# SA.net
KiCad netlist of a schematic drawn in EAGLE
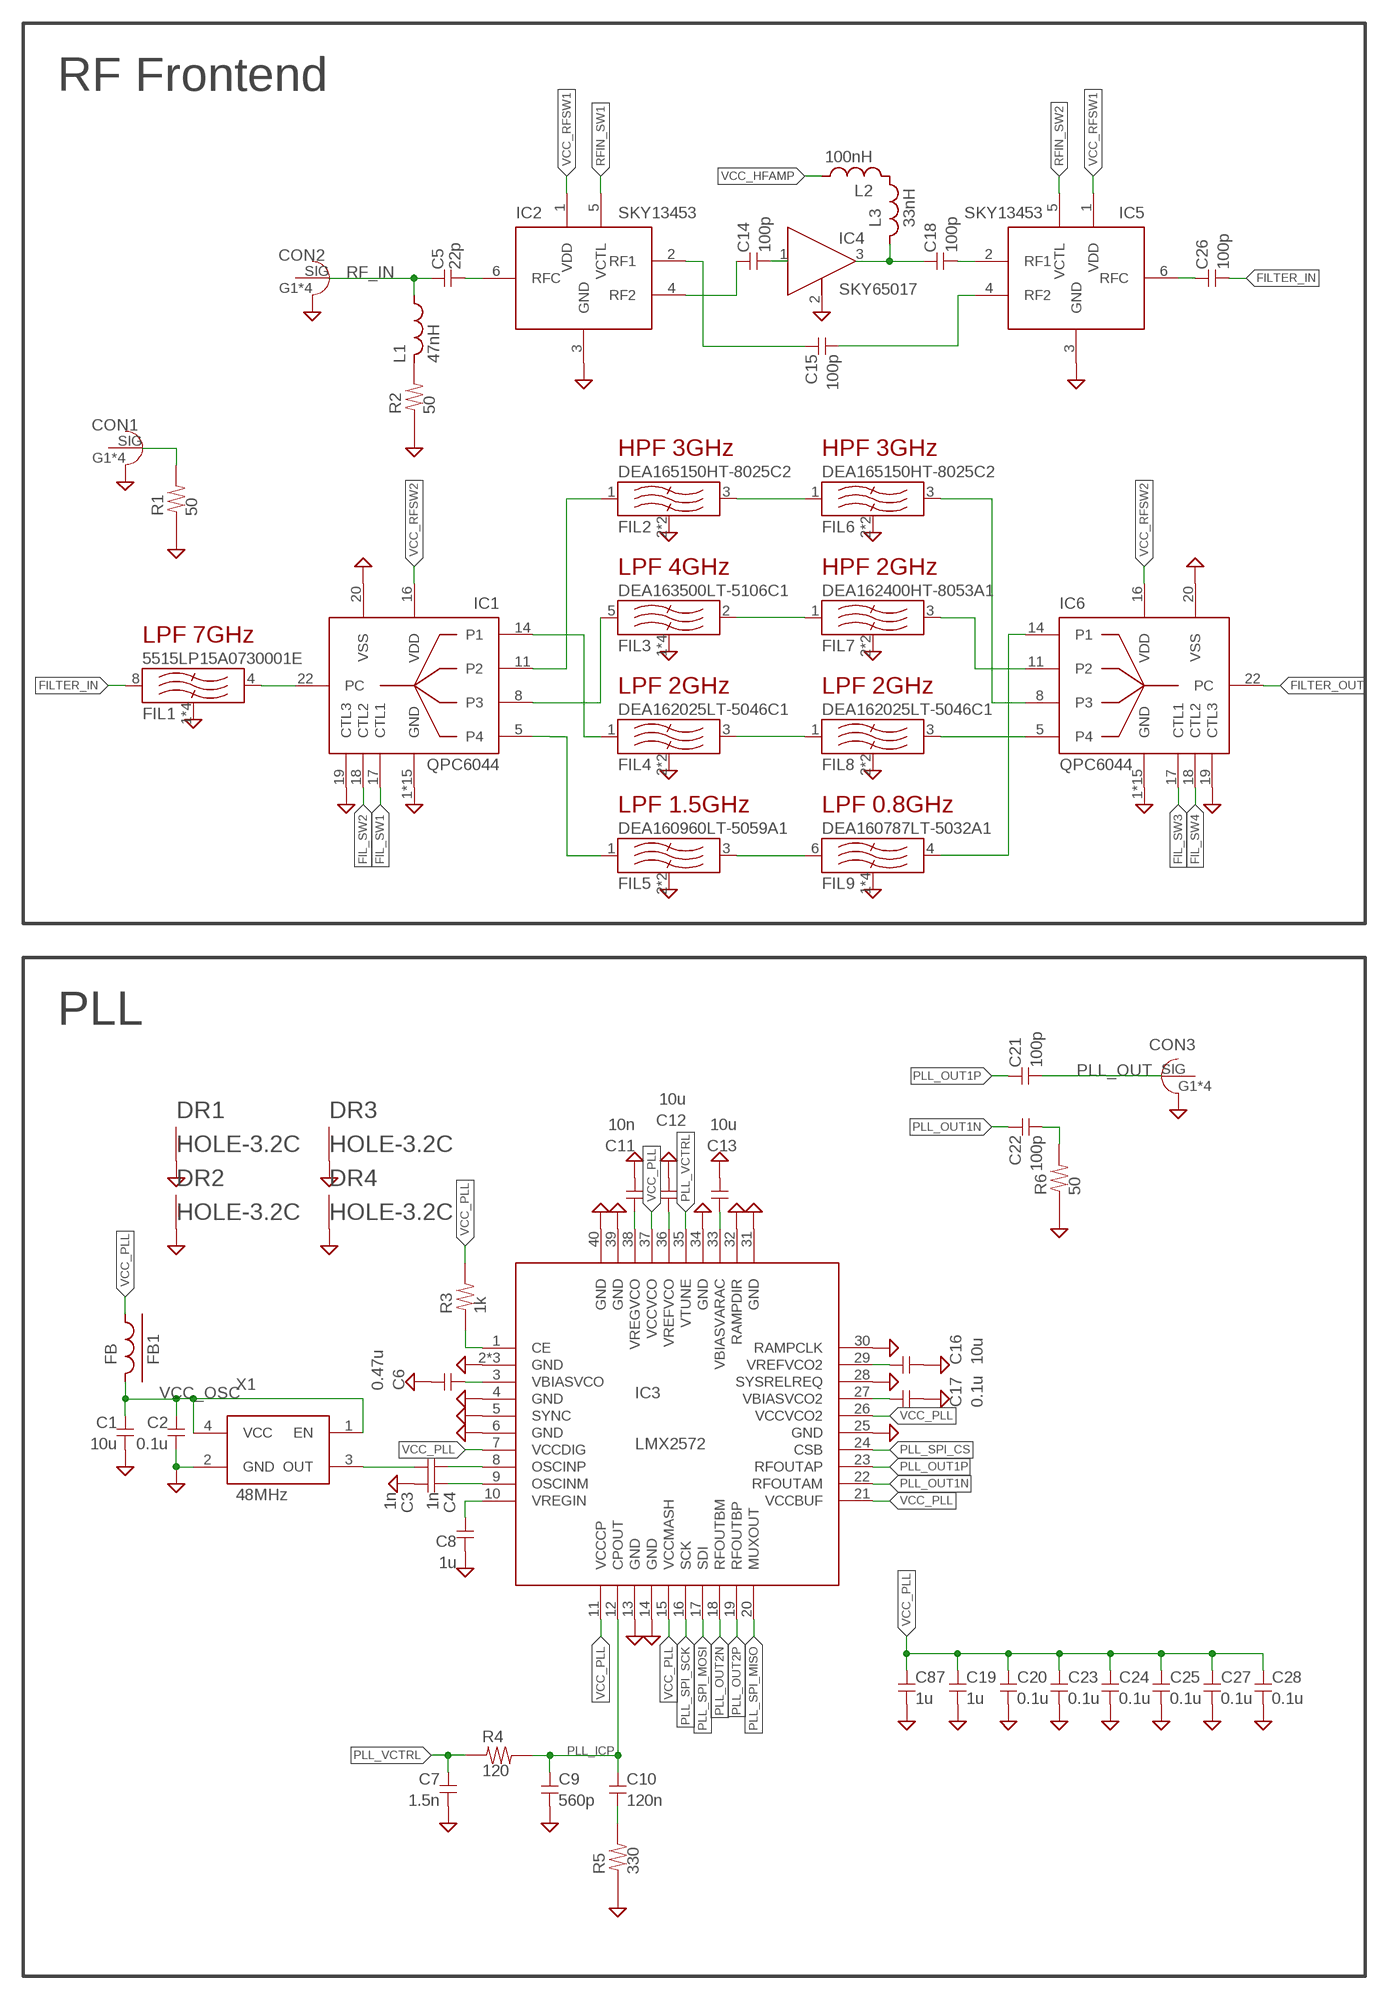
[diagram p0: schematic, sheet 1, part 1 of 2]
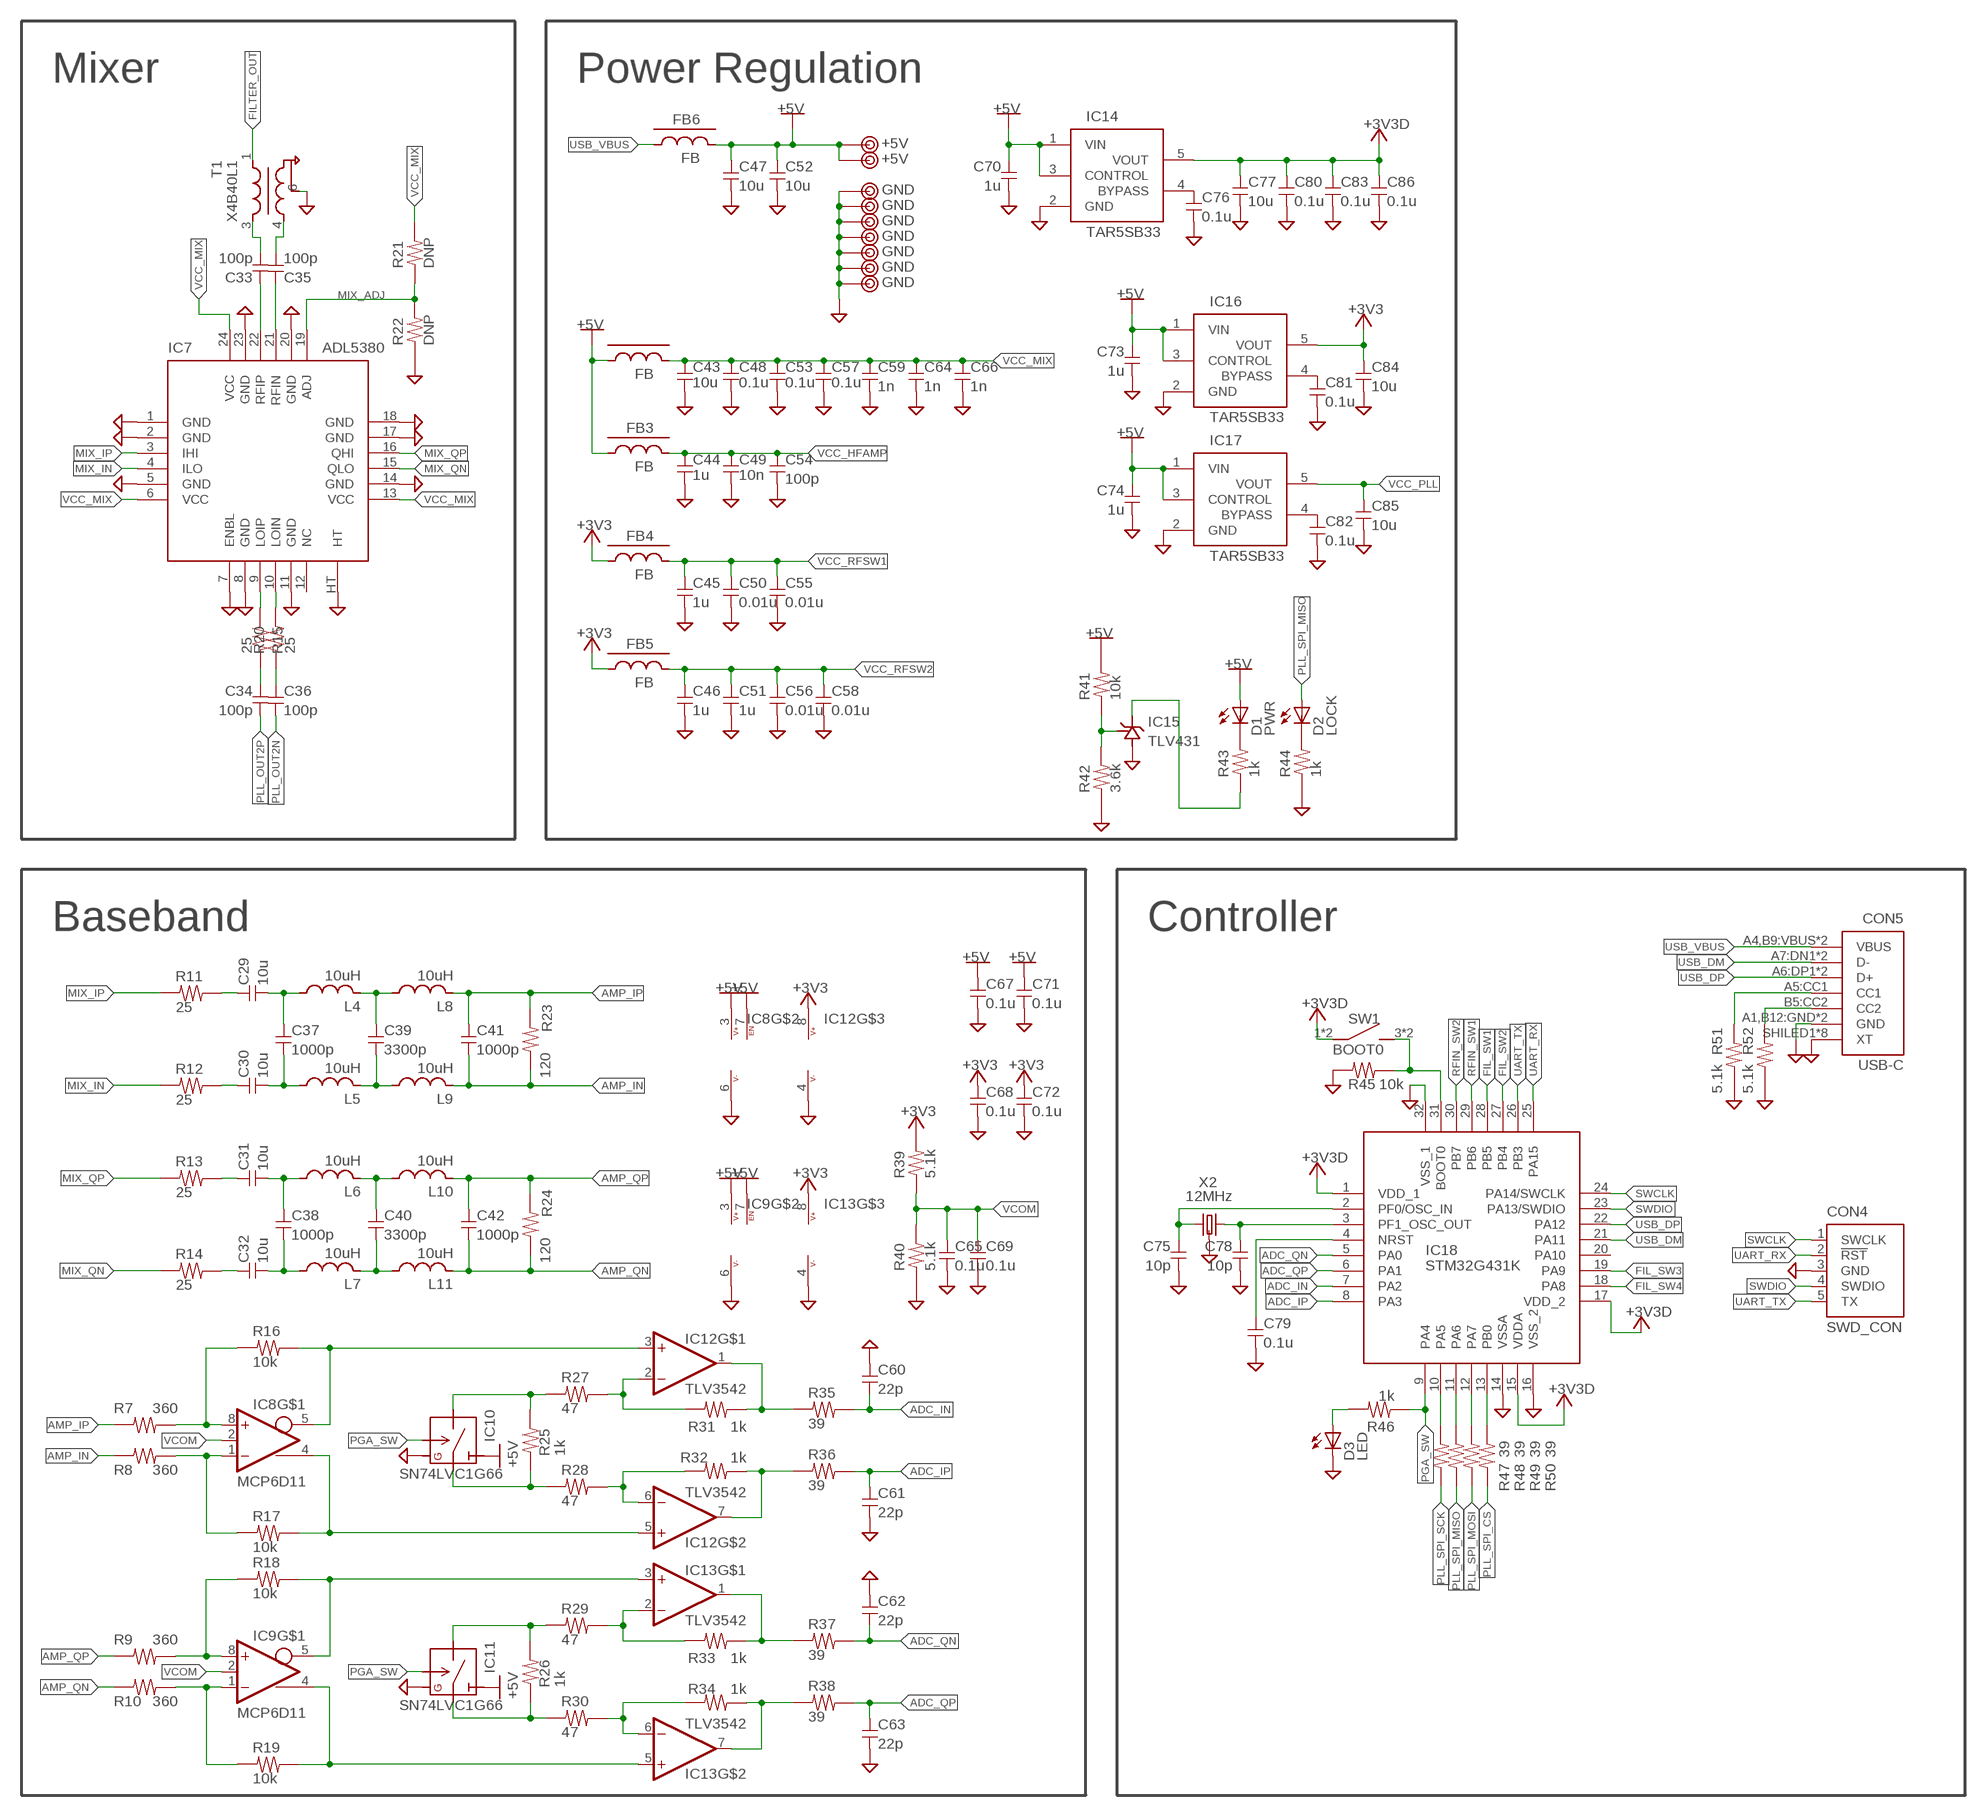
[diagram p1: schematic, sheet 1, part 2 of 2]

(export (version "E")
  (design (tool "Eeschema 10.0.6"))
  (components
    (comp (ref "C1")
      (value "10u")
      (footprint "eagle-import:2012")
      (libsource (lib "eagle-import") (part "C-2012"))
    )
    (comp (ref "C2")
      (value "0.1u")
      (footprint "eagle-import:1608C")
      (libsource (lib "eagle-import") (part "C-1608"))
    )
    (comp (ref "C3")
      (value "1n")
      (footprint "eagle-import:1005")
      (libsource (lib "eagle-import") (part "C-1005"))
    )
    (comp (ref "C4")
      (value "1n")
      (footprint "eagle-import:1005")
      (libsource (lib "eagle-import") (part "C-1005"))
    )
    (comp (ref "C5")
      (value "22p")
      (footprint "eagle-import:1005RF")
      (libsource (lib "eagle-import") (part "C-1005RF"))
    )
    (comp (ref "C6")
      (value "0.47u")
      (footprint "eagle-import:1608C")
      (libsource (lib "eagle-import") (part "C-1608"))
    )
    (comp (ref "C7")
      (value "1.5n")
      (footprint "eagle-import:1608C")
      (libsource (lib "eagle-import") (part "C-1608"))
    )
    (comp (ref "C8")
      (value "1u")
      (footprint "eagle-import:1608C")
      (libsource (lib "eagle-import") (part "C-1608"))
    )
    (comp (ref "C9")
      (value "560p")
      (footprint "eagle-import:1608C")
      (libsource (lib "eagle-import") (part "C-1608"))
    )
    (comp (ref "C10")
      (value "120n")
      (footprint "eagle-import:1608C")
      (libsource (lib "eagle-import") (part "C-1608"))
    )
    (comp (ref "C11")
      (value "10n")
      (footprint "eagle-import:1608C")
      (libsource (lib "eagle-import") (part "C-1608"))
    )
    (comp (ref "C12")
      (value "10u")
      (footprint "eagle-import:1608C")
      (libsource (lib "eagle-import") (part "C-1608"))
    )
    (comp (ref "C13")
      (value "10u")
      (footprint "eagle-import:1608C")
      (libsource (lib "eagle-import") (part "C-1608"))
    )
    (comp (ref "C14")
      (value "100p")
      (footprint "eagle-import:1005RF")
      (libsource (lib "eagle-import") (part "C-1005RF"))
    )
    (comp (ref "C15")
      (value "100p")
      (footprint "eagle-import:1005RF")
      (libsource (lib "eagle-import") (part "C-1005RF"))
    )
    (comp (ref "C16")
      (value "10u")
      (footprint "eagle-import:1608C")
      (libsource (lib "eagle-import") (part "C-1608"))
    )
    (comp (ref "C17")
      (value "0.1u")
      (footprint "eagle-import:1608C")
      (libsource (lib "eagle-import") (part "C-1608"))
    )
    (comp (ref "C18")
      (value "100p")
      (footprint "eagle-import:1005RF")
      (libsource (lib "eagle-import") (part "C-1005RF"))
    )
    (comp (ref "C19")
      (value "1u")
      (footprint "eagle-import:1608C")
      (libsource (lib "eagle-import") (part "C-1608"))
    )
    (comp (ref "C20")
      (value "0.1u")
      (footprint "eagle-import:1608C")
      (libsource (lib "eagle-import") (part "C-1608"))
    )
    (comp (ref "C21")
      (value "100p")
      (footprint "eagle-import:1005RF")
      (libsource (lib "eagle-import") (part "C-1005RF"))
    )
    (comp (ref "C22")
      (value "100p")
      (footprint "eagle-import:1005RF")
      (libsource (lib "eagle-import") (part "C-1005RF"))
    )
    (comp (ref "C23")
      (value "0.1u")
      (footprint "eagle-import:1608C")
      (libsource (lib "eagle-import") (part "C-1608"))
    )
    (comp (ref "C24")
      (value "0.1u")
      (footprint "eagle-import:1608C")
      (libsource (lib "eagle-import") (part "C-1608"))
    )
    (comp (ref "C25")
      (value "0.1u")
      (footprint "eagle-import:1608C")
      (libsource (lib "eagle-import") (part "C-1608"))
    )
    (comp (ref "C26")
      (value "100p")
      (footprint "eagle-import:1005RF")
      (libsource (lib "eagle-import") (part "C-1005RF"))
    )
    (comp (ref "C27")
      (value "0.1u")
      (footprint "eagle-import:1608C")
      (libsource (lib "eagle-import") (part "C-1608"))
    )
    (comp (ref "C28")
      (value "0.1u")
      (footprint "eagle-import:1608C")
      (libsource (lib "eagle-import") (part "C-1608"))
    )
    (comp (ref "C29")
      (value "10u")
      (footprint "eagle-import:1608C")
      (libsource (lib "eagle-import") (part "C-1608"))
    )
    (comp (ref "C30")
      (value "10u")
      (footprint "eagle-import:1608C")
      (libsource (lib "eagle-import") (part "C-1608"))
    )
    (comp (ref "C31")
      (value "10u")
      (footprint "eagle-import:1608C")
      (libsource (lib "eagle-import") (part "C-1608"))
    )
    (comp (ref "C32")
      (value "10u")
      (footprint "eagle-import:1608C")
      (libsource (lib "eagle-import") (part "C-1608"))
    )
    (comp (ref "C33")
      (value "100p")
      (footprint "eagle-import:1005RF")
      (libsource (lib "eagle-import") (part "C-1005RF"))
    )
    (comp (ref "C34")
      (value "100p")
      (footprint "eagle-import:1005RF")
      (libsource (lib "eagle-import") (part "C-1005RF"))
    )
    (comp (ref "C35")
      (value "100p")
      (footprint "eagle-import:1005RF")
      (libsource (lib "eagle-import") (part "C-1005RF"))
    )
    (comp (ref "C36")
      (value "100p")
      (footprint "eagle-import:1005RF")
      (libsource (lib "eagle-import") (part "C-1005RF"))
    )
    (comp (ref "C37")
      (value "1000p")
      (footprint "eagle-import:1608C")
      (libsource (lib "eagle-import") (part "C-1608"))
    )
    (comp (ref "C38")
      (value "1000p")
      (footprint "eagle-import:1608C")
      (libsource (lib "eagle-import") (part "C-1608"))
    )
    (comp (ref "C39")
      (value "3300p")
      (footprint "eagle-import:1608C")
      (libsource (lib "eagle-import") (part "C-1608"))
    )
    (comp (ref "C40")
      (value "3300p")
      (footprint "eagle-import:1608C")
      (libsource (lib "eagle-import") (part "C-1608"))
    )
    (comp (ref "C41")
      (value "1000p")
      (footprint "eagle-import:1608C")
      (libsource (lib "eagle-import") (part "C-1608"))
    )
    (comp (ref "C42")
      (value "1000p")
      (footprint "eagle-import:1608C")
      (libsource (lib "eagle-import") (part "C-1608"))
    )
    (comp (ref "C43")
      (value "10u")
      (footprint "eagle-import:2012")
      (libsource (lib "eagle-import") (part "C-2012"))
    )
    (comp (ref "C44")
      (value "1u")
      (footprint "eagle-import:1608C")
      (libsource (lib "eagle-import") (part "C-1608"))
    )
    (comp (ref "C45")
      (value "1u")
      (footprint "eagle-import:1608C")
      (libsource (lib "eagle-import") (part "C-1608"))
    )
    (comp (ref "C46")
      (value "1u")
      (footprint "eagle-import:1608C")
      (libsource (lib "eagle-import") (part "C-1608"))
    )
    (comp (ref "C47")
      (value "10u")
      (footprint "eagle-import:3216")
      (libsource (lib "eagle-import") (part "C-3216"))
    )
    (comp (ref "C48")
      (value "0.1u")
      (footprint "eagle-import:1608C")
      (libsource (lib "eagle-import") (part "C-1608"))
    )
    (comp (ref "C49")
      (value "10n")
      (footprint "eagle-import:1608C")
      (libsource (lib "eagle-import") (part "C-1608"))
    )
    (comp (ref "C50")
      (value "0.01u")
      (footprint "eagle-import:1608C")
      (libsource (lib "eagle-import") (part "C-1608"))
    )
    (comp (ref "C51")
      (value "1u")
      (footprint "eagle-import:1608C")
      (libsource (lib "eagle-import") (part "C-1608"))
    )
    (comp (ref "C52")
      (value "10u")
      (footprint "eagle-import:2012")
      (libsource (lib "eagle-import") (part "C-2012"))
    )
    (comp (ref "C53")
      (value "0.1u")
      (footprint "eagle-import:1608C")
      (libsource (lib "eagle-import") (part "C-1608"))
    )
    (comp (ref "C54")
      (value "100p")
      (footprint "eagle-import:1005")
      (libsource (lib "eagle-import") (part "C-1005"))
    )
    (comp (ref "C55")
      (value "0.01u")
      (footprint "eagle-import:1608C")
      (libsource (lib "eagle-import") (part "C-1608"))
    )
    (comp (ref "C56")
      (value "0.01u")
      (footprint "eagle-import:1608C")
      (libsource (lib "eagle-import") (part "C-1608"))
    )
    (comp (ref "C57")
      (value "0.1u")
      (footprint "eagle-import:1608C")
      (libsource (lib "eagle-import") (part "C-1608"))
    )
    (comp (ref "C58")
      (value "0.01u")
      (footprint "eagle-import:1608C")
      (libsource (lib "eagle-import") (part "C-1608"))
    )
    (comp (ref "C59")
      (value "1n")
      (footprint "eagle-import:1005")
      (libsource (lib "eagle-import") (part "C-1005"))
    )
    (comp (ref "C60")
      (value "22p")
      (footprint "eagle-import:1608C")
      (libsource (lib "eagle-import") (part "C-1608"))
    )
    (comp (ref "C61")
      (value "22p")
      (footprint "eagle-import:1608C")
      (libsource (lib "eagle-import") (part "C-1608"))
    )
    (comp (ref "C62")
      (value "22p")
      (footprint "eagle-import:1608C")
      (libsource (lib "eagle-import") (part "C-1608"))
    )
    (comp (ref "C63")
      (value "22p")
      (footprint "eagle-import:1608C")
      (libsource (lib "eagle-import") (part "C-1608"))
    )
    (comp (ref "C64")
      (value "1n")
      (footprint "eagle-import:1005")
      (libsource (lib "eagle-import") (part "C-1005"))
    )
    (comp (ref "C65")
      (value "0.1u")
      (footprint "eagle-import:1608C")
      (libsource (lib "eagle-import") (part "C-1608"))
    )
    (comp (ref "C66")
      (value "1n")
      (footprint "eagle-import:1005")
      (libsource (lib "eagle-import") (part "C-1005"))
    )
    (comp (ref "C67")
      (value "0.1u")
      (footprint "eagle-import:1608C")
      (libsource (lib "eagle-import") (part "C-1608"))
    )
    (comp (ref "C68")
      (value "0.1u")
      (footprint "eagle-import:1608C")
      (libsource (lib "eagle-import") (part "C-1608"))
    )
    (comp (ref "C69")
      (value "0.1u")
      (footprint "eagle-import:1608C")
      (libsource (lib "eagle-import") (part "C-1608"))
    )
    (comp (ref "C70")
      (value "1u")
      (footprint "eagle-import:1608C")
      (libsource (lib "eagle-import") (part "C-1608"))
    )
    (comp (ref "C71")
      (value "0.1u")
      (footprint "eagle-import:1608C")
      (libsource (lib "eagle-import") (part "C-1608"))
    )
    (comp (ref "C72")
      (value "0.1u")
      (footprint "eagle-import:1608C")
      (libsource (lib "eagle-import") (part "C-1608"))
    )
    (comp (ref "C73")
      (value "1u")
      (footprint "eagle-import:1608C")
      (libsource (lib "eagle-import") (part "C-1608"))
    )
    (comp (ref "C74")
      (value "1u")
      (footprint "eagle-import:1608C")
      (libsource (lib "eagle-import") (part "C-1608"))
    )
    (comp (ref "C75")
      (value "10p")
      (footprint "eagle-import:1608C")
      (libsource (lib "eagle-import") (part "C-1608"))
    )
    (comp (ref "C76")
      (value "0.1u")
      (footprint "eagle-import:1608C")
      (libsource (lib "eagle-import") (part "C-1608"))
    )
    (comp (ref "C77")
      (value "10u")
      (footprint "eagle-import:2012")
      (libsource (lib "eagle-import") (part "C-2012"))
    )
    (comp (ref "C78")
      (value "10p")
      (footprint "eagle-import:1608C")
      (libsource (lib "eagle-import") (part "C-1608"))
    )
    (comp (ref "C79")
      (value "0.1u")
      (footprint "eagle-import:1608C")
      (libsource (lib "eagle-import") (part "C-1608"))
    )
    (comp (ref "C80")
      (value "0.1u")
      (footprint "eagle-import:1608C")
      (libsource (lib "eagle-import") (part "C-1608"))
    )
    (comp (ref "C81")
      (value "0.1u")
      (footprint "eagle-import:1608C")
      (libsource (lib "eagle-import") (part "C-1608"))
    )
    (comp (ref "C82")
      (value "0.1u")
      (footprint "eagle-import:1608C")
      (libsource (lib "eagle-import") (part "C-1608"))
    )
    (comp (ref "C83")
      (value "0.1u")
      (footprint "eagle-import:1608C")
      (libsource (lib "eagle-import") (part "C-1608"))
    )
    (comp (ref "C84")
      (value "10u")
      (footprint "eagle-import:2012")
      (libsource (lib "eagle-import") (part "C-2012"))
    )
    (comp (ref "C85")
      (value "10u")
      (footprint "eagle-import:2012")
      (libsource (lib "eagle-import") (part "C-2012"))
    )
    (comp (ref "C86")
      (value "0.1u")
      (footprint "eagle-import:1608C")
      (libsource (lib "eagle-import") (part "C-1608"))
    )
    (comp (ref "C87")
      (value "1u")
      (footprint "eagle-import:1608C")
      (libsource (lib "eagle-import") (part "C-1608"))
    )
    (comp (ref "CON1")
      (value "DM_L")
      (footprint "eagle-import:SMA-EDGE")
      (libsource (lib "eagle-import") (part "SMA-142-0701-801"))
    )
    (comp (ref "CON2")
      (value "RF_IN")
      (footprint "eagle-import:SMA-EDGE")
      (libsource (lib "eagle-import") (part "SMA-142-0701-801"))
    )
    (comp (ref "CON3")
      (value "PLL_OUT")
      (footprint "eagle-import:SMA-EDGE")
      (libsource (lib "eagle-import") (part "SMA-142-0701-801"))
    )
    (comp (ref "CON4")
      (value "SWD_CON")
      (footprint "eagle-import:SWD_CON")
      (libsource (lib "eagle-import") (part "SWD_CON"))
    )
    (comp (ref "CON5")
      (value "USB-C")
      (footprint "eagle-import:5077CR-16-SMC2-BK-TR")
      (libsource (lib "eagle-import") (part "USB-C"))
    )
    (comp (ref "D1")
      (value "PWR")
      (footprint "eagle-import:D1608")
      (libsource (lib "eagle-import") (part "LED-SMD1608"))
    )
    (comp (ref "D2")
      (value "LOCK")
      (footprint "eagle-import:D1608")
      (libsource (lib "eagle-import") (part "LED-SMD1608"))
    )
    (comp (ref "D3")
      (value "LED")
      (footprint "eagle-import:D1608")
      (libsource (lib "eagle-import") (part "LED-SMD1608"))
    )
    (comp (ref "DR1")
      (value "HOLE-3.2C")
      (footprint "eagle-import:HOLE_3.2_CON2")
      (libsource (lib "eagle-import") (part "HOLE-3.2C"))
    )
    (comp (ref "DR2")
      (value "HOLE-3.2C")
      (footprint "eagle-import:HOLE_3.2_CON2")
      (libsource (lib "eagle-import") (part "HOLE-3.2C"))
    )
    (comp (ref "DR3")
      (value "HOLE-3.2C")
      (footprint "eagle-import:HOLE_3.2_CON2")
      (libsource (lib "eagle-import") (part "HOLE-3.2C"))
    )
    (comp (ref "DR4")
      (value "HOLE-3.2C")
      (footprint "eagle-import:HOLE_3.2_CON2")
      (libsource (lib "eagle-import") (part "HOLE-3.2C"))
    )
    (comp (ref "FB1")
      (value "FB")
      (footprint "eagle-import:1608-FB")
      (libsource (lib "eagle-import") (part "FB-1608FB"))
    )
    (comp (ref "FB2")
      (value "FB")
      (footprint "eagle-import:1608-FB")
      (libsource (lib "eagle-import") (part "FB-1608FB"))
    )
    (comp (ref "FB3")
      (value "FB")
      (footprint "eagle-import:1608-FB")
      (libsource (lib "eagle-import") (part "FB-1608FB"))
    )
    (comp (ref "FB4")
      (value "FB")
      (footprint "eagle-import:1608-FB")
      (libsource (lib "eagle-import") (part "FB-1608FB"))
    )
    (comp (ref "FB5")
      (value "FB")
      (footprint "eagle-import:1608-FB")
      (libsource (lib "eagle-import") (part "FB-1608FB"))
    )
    (comp (ref "FB6")
      (value "FB")
      (footprint "eagle-import:2012-R")
      (libsource (lib "eagle-import") (part "FB-2012-FB"))
    )
    (comp (ref "FIL1")
      (value "5515LP15A0730001E")
      (footprint "eagle-import:RF-FILTER-2012-JOHANSON")
      (libsource (lib "eagle-import") (part "RF-FILTER-2012-JOHANSON"))
    )
    (comp (ref "FIL2")
      (value "DEA165150HT-8025C2")
      (footprint "eagle-import:RF-FILTER-1608-TDK")
      (libsource (lib "eagle-import") (part "RF-FILTER-1608-TDK"))
    )
    (comp (ref "FIL3")
      (value "DEA163500LT-5106C1")
      (footprint "eagle-import:RF-FILTER-1608-TDK2")
      (libsource (lib "eagle-import") (part "RF-FILTER-1608-TDK3"))
    )
    (comp (ref "FIL4")
      (value "DEA162025LT-5046C1")
      (footprint "eagle-import:RF-FILTER-1608-TDK")
      (libsource (lib "eagle-import") (part "RF-FILTER-1608-TDK"))
    )
    (comp (ref "FIL5")
      (value "DEA160960LT-5059A1")
      (footprint "eagle-import:RF-FILTER-1608-TDK")
      (libsource (lib "eagle-import") (part "RF-FILTER-1608-TDK"))
    )
    (comp (ref "FIL6")
      (value "DEA165150HT-8025C2")
      (footprint "eagle-import:RF-FILTER-1608-TDK")
      (libsource (lib "eagle-import") (part "RF-FILTER-1608-TDK"))
    )
    (comp (ref "FIL7")
      (value "DEA162400HT-8053A1")
      (footprint "eagle-import:RF-FILTER-1608-TDK")
      (libsource (lib "eagle-import") (part "RF-FILTER-1608-TDK"))
    )
    (comp (ref "FIL8")
      (value "DEA162025LT-5046C1")
      (footprint "eagle-import:RF-FILTER-1608-TDK")
      (libsource (lib "eagle-import") (part "RF-FILTER-1608-TDK"))
    )
    (comp (ref "FIL9")
      (value "DEA160787LT-5032A1")
      (footprint "eagle-import:RF-FILTER-1608-TDK2")
      (libsource (lib "eagle-import") (part "RF-FILTER-1608-TDK2"))
    )
    (comp (ref "IC1")
      (value "QPC6044")
      (footprint "eagle-import:QFN24-QPC6044")
      (libsource (lib "eagle-import") (part "QPC6044"))
    )
    (comp (ref "IC2")
      (value "SKY13453")
      (footprint "eagle-import:SKY13453")
      (libsource (lib "eagle-import") (part "SKY13453"))
    )
    (comp (ref "IC3")
      (value "LMX2572")
      (footprint "eagle-import:QFN40-LMX")
      (libsource (lib "eagle-import") (part "LMX2572"))
    )
    (comp (ref "IC4")
      (value "SKY65017")
      (footprint "eagle-import:SOT89-RF")
      (libsource (lib "eagle-import") (part "RF_AMP"))
    )
    (comp (ref "IC5")
      (value "SKY13453")
      (footprint "eagle-import:SKY13453")
      (libsource (lib "eagle-import") (part "SKY13453"))
    )
    (comp (ref "IC6")
      (value "QPC6044")
      (footprint "eagle-import:QFN24-QPC6044")
      (libsource (lib "eagle-import") (part "QPC6044"))
    )
    (comp (ref "IC7")
      (value "ADL5380")
      (footprint "eagle-import:LFCSP24")
      (libsource (lib "eagle-import") (part "ADL5380"))
    )
    (comp (ref "IC8")
      (value "MCP6D11")
      (footprint "eagle-import:MSOP8")
      (libsource (lib "eagle-import") (part "OPA-DIFF-MSOP"))
    )
    (comp (ref "IC9")
      (value "MCP6D11")
      (footprint "eagle-import:MSOP8")
      (libsource (lib "eagle-import") (part "OPA-DIFF-MSOP"))
    )
    (comp (ref "IC10")
      (value "SN74LVC1G66")
      (footprint "eagle-import:SOT23-5-2")
      (libsource (lib "eagle-import") (part "SN74LVC1G66"))
    )
    (comp (ref "IC11")
      (value "SN74LVC1G66")
      (footprint "eagle-import:SOT23-5-2")
      (libsource (lib "eagle-import") (part "SN74LVC1G66"))
    )
    (comp (ref "IC12")
      (value "TLV3542")
      (footprint "eagle-import:SOP8-3")
      (libsource (lib "eagle-import") (part "OPA-2-SOP"))
    )
    (comp (ref "IC13")
      (value "TLV3542")
      (footprint "eagle-import:SOP8-3")
      (libsource (lib "eagle-import") (part "OPA-2-SOP"))
    )
    (comp (ref "IC14")
      (value "TAR5SB33")
      (footprint "eagle-import:SOT23-5")
      (libsource (lib "eagle-import") (part "TAR5SB33"))
    )
    (comp (ref "IC15")
      (value "TLV431")
      (footprint "eagle-import:SC59")
      (libsource (lib "eagle-import") (part "TL431-SC59"))
    )
    (comp (ref "IC16")
      (value "TAR5SB33")
      (footprint "eagle-import:SOT23-5")
      (libsource (lib "eagle-import") (part "TAR5SB33"))
    )
    (comp (ref "IC17")
      (value "TAR5SB33")
      (footprint "eagle-import:SOT23-5")
      (libsource (lib "eagle-import") (part "TAR5SB33"))
    )
    (comp (ref "IC18")
      (value "STM32G431K")
      (footprint "eagle-import:TQFP32-08")
      (libsource (lib "eagle-import") (part "STM32G431KB"))
    )
    (comp (ref "L1")
      (value "47nH")
      (footprint "eagle-import:1005RF")
      (libsource (lib "eagle-import") (part "L-1005RF"))
    )
    (comp (ref "L2")
      (value "100nH")
      (footprint "eagle-import:1608-L")
      (libsource (lib "eagle-import") (part "L-1608"))
    )
    (comp (ref "L3")
      (value "33nH")
      (footprint "eagle-import:1005RF")
      (libsource (lib "eagle-import") (part "L-1005RF"))
    )
    (comp (ref "L4")
      (value "10uH")
      (footprint "eagle-import:2012-R")
      (libsource (lib "eagle-import") (part "L-2012"))
    )
    (comp (ref "L5")
      (value "10uH")
      (footprint "eagle-import:2012-R")
      (libsource (lib "eagle-import") (part "L-2012"))
    )
    (comp (ref "L6")
      (value "10uH")
      (footprint "eagle-import:2012-R")
      (libsource (lib "eagle-import") (part "L-2012"))
    )
    (comp (ref "L7")
      (value "10uH")
      (footprint "eagle-import:2012-R")
      (libsource (lib "eagle-import") (part "L-2012"))
    )
    (comp (ref "L8")
      (value "10uH")
      (footprint "eagle-import:2012-R")
      (libsource (lib "eagle-import") (part "L-2012"))
    )
    (comp (ref "L9")
      (value "10uH")
      (footprint "eagle-import:2012-R")
      (libsource (lib "eagle-import") (part "L-2012"))
    )
    (comp (ref "L10")
      (value "10uH")
      (footprint "eagle-import:2012-R")
      (libsource (lib "eagle-import") (part "L-2012"))
    )
    (comp (ref "L11")
      (value "10uH")
      (footprint "eagle-import:2012-R")
      (libsource (lib "eagle-import") (part "L-2012"))
    )
    (comp (ref "R1")
      (value "50")
      (footprint "eagle-import:1005RF")
      (libsource (lib "eagle-import") (part "R-1005RF"))
    )
    (comp (ref "R2")
      (value "50")
      (footprint "eagle-import:1005RF")
      (libsource (lib "eagle-import") (part "R-1005RF"))
    )
    (comp (ref "R3")
      (value "1k")
      (footprint "eagle-import:1608")
      (libsource (lib "eagle-import") (part "R-1608"))
    )
    (comp (ref "R4")
      (value "120")
      (footprint "eagle-import:1608")
      (libsource (lib "eagle-import") (part "R-1608"))
    )
    (comp (ref "R5")
      (value "330")
      (footprint "eagle-import:1608")
      (libsource (lib "eagle-import") (part "R-1608"))
    )
    (comp (ref "R6")
      (value "50")
      (footprint "eagle-import:1005RF")
      (libsource (lib "eagle-import") (part "R-1005RF"))
    )
    (comp (ref "R7")
      (value "360")
      (footprint "eagle-import:1608")
      (libsource (lib "eagle-import") (part "R-1608"))
    )
    (comp (ref "R8")
      (value "360")
      (footprint "eagle-import:1608")
      (libsource (lib "eagle-import") (part "R-1608"))
    )
    (comp (ref "R9")
      (value "360")
      (footprint "eagle-import:1608")
      (libsource (lib "eagle-import") (part "R-1608"))
    )
    (comp (ref "R10")
      (value "360")
      (footprint "eagle-import:1608")
      (libsource (lib "eagle-import") (part "R-1608"))
    )
    (comp (ref "R11")
      (value "25")
      (footprint "eagle-import:1608")
      (libsource (lib "eagle-import") (part "R-1608"))
    )
    (comp (ref "R12")
      (value "25")
      (footprint "eagle-import:1608")
      (libsource (lib "eagle-import") (part "R-1608"))
    )
    (comp (ref "R13")
      (value "25")
      (footprint "eagle-import:1608")
      (libsource (lib "eagle-import") (part "R-1608"))
    )
    (comp (ref "R14")
      (value "25")
      (footprint "eagle-import:1608")
      (libsource (lib "eagle-import") (part "R-1608"))
    )
    (comp (ref "R15")
      (value "25")
      (footprint "eagle-import:1005RF")
      (libsource (lib "eagle-import") (part "R-1005RF"))
    )
    (comp (ref "R16")
      (value "10k")
      (footprint "eagle-import:1608")
      (libsource (lib "eagle-import") (part "R-1608"))
    )
    (comp (ref "R17")
      (value "10k")
      (footprint "eagle-import:1608-3")
      (libsource (lib "eagle-import") (part "R-1608-3"))
    )
    (comp (ref "R18")
      (value "10k")
      (footprint "eagle-import:1608")
      (libsource (lib "eagle-import") (part "R-1608"))
    )
    (comp (ref "R19")
      (value "10k")
      (footprint "eagle-import:1608-3")
      (libsource (lib "eagle-import") (part "R-1608-3"))
    )
    (comp (ref "R20")
      (value "25")
      (footprint "eagle-import:1005RF")
      (libsource (lib "eagle-import") (part "R-1005RF"))
    )
    (comp (ref "R21")
      (value "DNP")
      (footprint "eagle-import:1608")
      (libsource (lib "eagle-import") (part "R-1608"))
    )
    (comp (ref "R22")
      (value "DNP")
      (footprint "eagle-import:1608")
      (libsource (lib "eagle-import") (part "R-1608"))
    )
    (comp (ref "R23")
      (value "120")
      (footprint "eagle-import:1608")
      (libsource (lib "eagle-import") (part "R-1608"))
    )
    (comp (ref "R24")
      (value "120")
      (footprint "eagle-import:1608")
      (libsource (lib "eagle-import") (part "R-1608"))
    )
    (comp (ref "R25")
      (value "1k")
      (footprint "eagle-import:1608")
      (libsource (lib "eagle-import") (part "R-1608"))
    )
    (comp (ref "R26")
      (value "1k")
      (footprint "eagle-import:1608")
      (libsource (lib "eagle-import") (part "R-1608"))
    )
    (comp (ref "R27")
      (value "47")
      (footprint "eagle-import:1608-3")
      (libsource (lib "eagle-import") (part "R-1608-3"))
    )
    (comp (ref "R28")
      (value "47")
      (footprint "eagle-import:1608-3")
      (libsource (lib "eagle-import") (part "R-1608-3"))
    )
    (comp (ref "R29")
      (value "47")
      (footprint "eagle-import:1608-3")
      (libsource (lib "eagle-import") (part "R-1608-3"))
    )
    (comp (ref "R30")
      (value "47")
      (footprint "eagle-import:1608-3")
      (libsource (lib "eagle-import") (part "R-1608-3"))
    )
    (comp (ref "R31")
      (value "1k")
      (footprint "eagle-import:1608-3")
      (libsource (lib "eagle-import") (part "R-1608-3"))
    )
    (comp (ref "R32")
      (value "1k")
      (footprint "eagle-import:1608-3")
      (libsource (lib "eagle-import") (part "R-1608-3"))
    )
    (comp (ref "R33")
      (value "1k")
      (footprint "eagle-import:1608-3")
      (libsource (lib "eagle-import") (part "R-1608-3"))
    )
    (comp (ref "R34")
      (value "1k")
      (footprint "eagle-import:1608-3")
      (libsource (lib "eagle-import") (part "R-1608-3"))
    )
    (comp (ref "R35")
      (value "39")
      (footprint "eagle-import:1608")
      (libsource (lib "eagle-import") (part "R-1608"))
    )
    (comp (ref "R36")
      (value "39")
      (footprint "eagle-import:1608")
      (libsource (lib "eagle-import") (part "R-1608"))
    )
    (comp (ref "R37")
      (value "39")
      (footprint "eagle-import:1608")
      (libsource (lib "eagle-import") (part "R-1608"))
    )
    (comp (ref "R38")
      (value "39")
      (footprint "eagle-import:1608")
      (libsource (lib "eagle-import") (part "R-1608"))
    )
    (comp (ref "R39")
      (value "5.1k")
      (footprint "eagle-import:1608")
      (libsource (lib "eagle-import") (part "R-1608"))
    )
    (comp (ref "R40")
      (value "5.1k")
      (footprint "eagle-import:1608")
      (libsource (lib "eagle-import") (part "R-1608"))
    )
    (comp (ref "R41")
      (value "10k")
      (footprint "eagle-import:1608")
      (libsource (lib "eagle-import") (part "R-1608"))
    )
    (comp (ref "R42")
      (value "3.6k")
      (footprint "eagle-import:1608")
      (libsource (lib "eagle-import") (part "R-1608"))
    )
    (comp (ref "R43")
      (value "1k")
      (footprint "eagle-import:1608")
      (libsource (lib "eagle-import") (part "R-1608"))
    )
    (comp (ref "R44")
      (value "1k")
      (footprint "eagle-import:1608")
      (libsource (lib "eagle-import") (part "R-1608"))
    )
    (comp (ref "R45")
      (value "10k")
      (footprint "eagle-import:1608")
      (libsource (lib "eagle-import") (part "R-1608"))
    )
    (comp (ref "R46")
      (value "1k")
      (footprint "eagle-import:1608")
      (libsource (lib "eagle-import") (part "R-1608"))
    )
    (comp (ref "R47")
      (value "39")
      (footprint "eagle-import:1608")
      (libsource (lib "eagle-import") (part "R-1608"))
    )
    (comp (ref "R48")
      (value "39")
      (footprint "eagle-import:1608")
      (libsource (lib "eagle-import") (part "R-1608"))
    )
    (comp (ref "R49")
      (value "39")
      (footprint "eagle-import:1608")
      (libsource (lib "eagle-import") (part "R-1608"))
    )
    (comp (ref "R50")
      (value "39")
      (footprint "eagle-import:1608")
      (libsource (lib "eagle-import") (part "R-1608"))
    )
    (comp (ref "R51")
      (value "5.1k")
      (footprint "eagle-import:1608")
      (libsource (lib "eagle-import") (part "R-1608"))
    )
    (comp (ref "R52")
      (value "5.1k")
      (footprint "eagle-import:1608")
      (libsource (lib "eagle-import") (part "R-1608"))
    )
    (comp (ref "SW1")
      (value "BOOT0")
      (footprint "eagle-import:SKRPACE010")
      (libsource (lib "eagle-import") (part "SW-SMD"))
    )
    (comp (ref "T1")
      (value "X4B40L1")
      (footprint "eagle-import:X4B40L1")
      (libsource (lib "eagle-import") (part "X4B40L1"))
    )
    (comp (ref "TP1")
      (value "+5V")
      (footprint "eagle-import:TESTPIN")
      (libsource (lib "eagle-import") (part "TESTPIN"))
    )
    (comp (ref "TP2")
      (value "GND")
      (footprint "eagle-import:TESTPIN")
      (libsource (lib "eagle-import") (part "TESTPIN"))
    )
    (comp (ref "TP3")
      (value "GND")
      (footprint "eagle-import:TESTPIN")
      (libsource (lib "eagle-import") (part "TESTPIN"))
    )
    (comp (ref "TP4")
      (value "+5V")
      (footprint "eagle-import:TESTPIN")
      (libsource (lib "eagle-import") (part "TESTPIN"))
    )
    (comp (ref "TP5")
      (value "GND")
      (footprint "eagle-import:TESTPIN")
      (libsource (lib "eagle-import") (part "TESTPIN"))
    )
    (comp (ref "TP6")
      (value "GND")
      (footprint "eagle-import:TESTPIN")
      (libsource (lib "eagle-import") (part "TESTPIN"))
    )
    (comp (ref "TP7")
      (value "GND")
      (footprint "eagle-import:TESTPIN")
      (libsource (lib "eagle-import") (part "TESTPIN"))
    )
    (comp (ref "TP8")
      (value "GND")
      (footprint "eagle-import:TESTPIN")
      (libsource (lib "eagle-import") (part "TESTPIN"))
    )
    (comp (ref "TP9")
      (value "GND")
      (footprint "eagle-import:TESTPIN")
      (libsource (lib "eagle-import") (part "TESTPIN"))
    )
    (comp (ref "X1")
      (value "48MHz")
      (footprint "eagle-import:KC3225")
      (libsource (lib "eagle-import") (part "OSC-KC3225"))
    )
    (comp (ref "X2")
      (value "12MHz")
      (footprint "eagle-import:KC3225-CRYSTAL")
      (libsource (lib "eagle-import") (part "CRYSTAL2"))
    )
  )
  (nets
    (net (code "1") (name "+3V3") (class "Default")
      (node (ref "C68") (pin "1") (pinfunction "1_1") (pintype "passive"))
      (node (ref "C72") (pin "1") (pinfunction "1_1") (pintype "passive"))
      (node (ref "C84") (pin "1") (pinfunction "1_1") (pintype "passive"))
      (node (ref "FB4") (pin "1") (pinfunction "1_1") (pintype "passive"))
      (node (ref "FB5") (pin "1") (pinfunction "1_1") (pintype "passive"))
      (node (ref "IC12") (pin "8") (pinfunction "V+_8") (pintype "input"))
      (node (ref "IC13") (pin "8") (pinfunction "V+_8") (pintype "input"))
      (node (ref "IC16") (pin "5") (pinfunction "VOUT_5") (pintype "output"))
      (node (ref "R39") (pin "2") (pinfunction "2_2") (pintype "passive"))
    )
    (net (code "2") (name "+3V3D") (class "Default")
      (node (ref "C77") (pin "1") (pinfunction "1_1") (pintype "passive"))
      (node (ref "C80") (pin "1") (pinfunction "1_1") (pintype "passive"))
      (node (ref "C83") (pin "1") (pinfunction "1_1") (pintype "passive"))
      (node (ref "C86") (pin "1") (pinfunction "1_1") (pintype "passive"))
      (node (ref "IC14") (pin "5") (pinfunction "VOUT_5") (pintype "output"))
      (node (ref "IC18") (pin "1") (pinfunction "VDD_1_1") (pintype "power_in"))
      (node (ref "IC18") (pin "15") (pinfunction "VDDA_15") (pintype "power_in"))
      (node (ref "IC18") (pin "17") (pinfunction "VDD_2_17") (pintype "power_in"))
      (node (ref "SW1") (pin "1") (pinfunction "1_1") (pintype "passive"))
      (node (ref "SW1") (pin "2") (pinfunction "1_2") (pintype "passive"))
    )
    (net (code "3") (name "+5V") (class "Default")
      (node (ref "C47") (pin "1") (pinfunction "1_1") (pintype "passive"))
      (node (ref "C52") (pin "1") (pinfunction "1_1") (pintype "passive"))
      (node (ref "C67") (pin "1") (pinfunction "1_1") (pintype "passive"))
      (node (ref "C70") (pin "1") (pinfunction "1_1") (pintype "passive"))
      (node (ref "C71") (pin "1") (pinfunction "1_1") (pintype "passive"))
      (node (ref "C73") (pin "1") (pinfunction "1_1") (pintype "passive"))
      (node (ref "C74") (pin "1") (pinfunction "1_1") (pintype "passive"))
      (node (ref "D1") (pin "A") (pinfunction "A_A") (pintype "passive"))
      (node (ref "FB2") (pin "1") (pinfunction "1_1") (pintype "passive"))
      (node (ref "FB3") (pin "1") (pinfunction "1_1") (pintype "passive"))
      (node (ref "FB6") (pin "2") (pinfunction "2_2") (pintype "passive"))
      (node (ref "IC10") (pin "5") (pinfunction "VCC_5") (pintype "input"))
      (node (ref "IC11") (pin "5") (pinfunction "VCC_5") (pintype "input"))
      (node (ref "IC14") (pin "1") (pinfunction "VIN_1") (pintype "input"))
      (node (ref "IC14") (pin "3") (pinfunction "CONTROL_3") (pintype "input"))
      (node (ref "IC16") (pin "1") (pinfunction "VIN_1") (pintype "input"))
      (node (ref "IC16") (pin "3") (pinfunction "CONTROL_3") (pintype "input"))
      (node (ref "IC17") (pin "1") (pinfunction "VIN_1") (pintype "input"))
      (node (ref "IC17") (pin "3") (pinfunction "CONTROL_3") (pintype "input"))
      (node (ref "IC8") (pin "3") (pinfunction "V+_3") (pintype "input"))
      (node (ref "IC8") (pin "7") (pinfunction "EN_7") (pintype "input"))
      (node (ref "IC9") (pin "3") (pinfunction "V+_3") (pintype "input"))
      (node (ref "IC9") (pin "7") (pinfunction "EN_7") (pintype "input"))
      (node (ref "R41") (pin "2") (pinfunction "2_2") (pintype "passive"))
      (node (ref "TP1") (pin "1") (pinfunction "1_1") (pintype "passive"))
      (node (ref "TP4") (pin "1") (pinfunction "1_1") (pintype "passive"))
    )
    (net (code "4") (name "/MIX_ADJ") (class "Default")
      (node (ref "IC7") (pin "19") (pinfunction "ADJ_19") (pintype "bidirectional"))
      (node (ref "R21") (pin "1") (pinfunction "1_1") (pintype "passive"))
      (node (ref "R22") (pin "2") (pinfunction "2_2") (pintype "passive"))
    )
    (net (code "5") (name "/PLL_ICP") (class "Default")
      (node (ref "C10") (pin "1") (pinfunction "1_1") (pintype "passive"))
      (node (ref "C9") (pin "1") (pinfunction "1_1") (pintype "passive"))
      (node (ref "IC3") (pin "12") (pinfunction "CPOUT_12") (pintype "output"))
      (node (ref "R4") (pin "2") (pinfunction "2_2") (pintype "passive"))
    )
    (net (code "6") (name "/PLL_OUT") (class "Default")
      (node (ref "C21") (pin "2") (pinfunction "2_2") (pintype "passive"))
      (node (ref "CON3") (pin "SIG") (pinfunction "SIG_SIG") (pintype "passive"))
    )
    (net (code "7") (name "/RF_IN") (class "Default")
      (node (ref "C5") (pin "1") (pinfunction "1_1") (pintype "passive"))
      (node (ref "CON2") (pin "SIG") (pinfunction "SIG_SIG") (pintype "passive"))
      (node (ref "L1") (pin "1") (pinfunction "1_1") (pintype "passive"))
    )
    (net (code "8") (name "/VCC_OSC") (class "Default")
      (node (ref "C1") (pin "1") (pinfunction "1_1") (pintype "passive"))
      (node (ref "C2") (pin "1") (pinfunction "1_1") (pintype "passive"))
      (node (ref "FB1") (pin "2") (pinfunction "2_2") (pintype "passive"))
      (node (ref "X1") (pin "1") (pinfunction "EN_1") (pintype "input"))
      (node (ref "X1") (pin "4") (pinfunction "VCC_4") (pintype "input"))
    )
    (net (code "9") (name "ADC_IN") (class "Default")
      (node (ref "C60") (pin "2") (pinfunction "2_2") (pintype "passive"))
      (node (ref "IC18") (pin "7") (pinfunction "PA2_7") (pintype "bidirectional"))
      (node (ref "R35") (pin "2") (pinfunction "2_2") (pintype "passive"))
    )
    (net (code "10") (name "ADC_IP") (class "Default")
      (node (ref "C61") (pin "1") (pinfunction "1_1") (pintype "passive"))
      (node (ref "IC18") (pin "8") (pinfunction "PA3_8") (pintype "bidirectional"))
      (node (ref "R36") (pin "2") (pinfunction "2_2") (pintype "passive"))
    )
    (net (code "11") (name "ADC_QN") (class "Default")
      (node (ref "C62") (pin "2") (pinfunction "2_2") (pintype "passive"))
      (node (ref "IC18") (pin "5") (pinfunction "PA0_5") (pintype "bidirectional"))
      (node (ref "R37") (pin "2") (pinfunction "2_2") (pintype "passive"))
    )
    (net (code "12") (name "ADC_QP") (class "Default")
      (node (ref "C63") (pin "1") (pinfunction "1_1") (pintype "passive"))
      (node (ref "IC18") (pin "6") (pinfunction "PA1_6") (pintype "bidirectional"))
      (node (ref "R38") (pin "2") (pinfunction "2_2") (pintype "passive"))
    )
    (net (code "13") (name "AMP_IN") (class "Default")
      (node (ref "C41") (pin "2") (pinfunction "2_2") (pintype "passive"))
      (node (ref "L9") (pin "2") (pinfunction "2_2") (pintype "passive"))
      (node (ref "R23") (pin "1") (pinfunction "1_1") (pintype "passive"))
      (node (ref "R8") (pin "1") (pinfunction "1_1") (pintype "passive"))
    )
    (net (code "14") (name "AMP_IP") (class "Default")
      (node (ref "C41") (pin "1") (pinfunction "1_1") (pintype "passive"))
      (node (ref "L8") (pin "2") (pinfunction "2_2") (pintype "passive"))
      (node (ref "R23") (pin "2") (pinfunction "2_2") (pintype "passive"))
      (node (ref "R7") (pin "1") (pinfunction "1_1") (pintype "passive"))
    )
    (net (code "15") (name "AMP_QN") (class "Default")
      (node (ref "C42") (pin "2") (pinfunction "2_2") (pintype "passive"))
      (node (ref "L11") (pin "2") (pinfunction "2_2") (pintype "passive"))
      (node (ref "R10") (pin "1") (pinfunction "1_1") (pintype "passive"))
      (node (ref "R24") (pin "1") (pinfunction "1_1") (pintype "passive"))
    )
    (net (code "16") (name "AMP_QP") (class "Default")
      (node (ref "C42") (pin "1") (pinfunction "1_1") (pintype "passive"))
      (node (ref "L10") (pin "2") (pinfunction "2_2") (pintype "passive"))
      (node (ref "R24") (pin "2") (pinfunction "2_2") (pintype "passive"))
      (node (ref "R9") (pin "1") (pinfunction "1_1") (pintype "passive"))
    )
    (net (code "17") (name "FILTER_IN") (class "Default")
      (node (ref "C26") (pin "2") (pinfunction "2_2") (pintype "passive"))
      (node (ref "FIL1") (pin "8") (pinfunction "IN_8") (pintype "input"))
    )
    (net (code "18") (name "FILTER_OUT") (class "Default")
      (node (ref "IC6") (pin "22") (pinfunction "PC_22") (pintype "bidirectional"))
      (node (ref "T1") (pin "1") (pinfunction "IN_1") (pintype "passive"))
    )
    (net (code "19") (name "FIL_SW1") (class "Default")
      (node (ref "IC1") (pin "17") (pinfunction "CTL1_17") (pintype "input"))
      (node (ref "IC18") (pin "28") (pinfunction "PB5_28") (pintype "bidirectional"))
    )
    (net (code "20") (name "FIL_SW2") (class "Default")
      (node (ref "IC1") (pin "18") (pinfunction "CTL2_18") (pintype "input"))
      (node (ref "IC18") (pin "27") (pinfunction "PB4_27") (pintype "bidirectional"))
    )
    (net (code "21") (name "FIL_SW3") (class "Default")
      (node (ref "IC18") (pin "19") (pinfunction "PA9_19") (pintype "bidirectional"))
      (node (ref "IC6") (pin "17") (pinfunction "CTL1_17") (pintype "input"))
    )
    (net (code "22") (name "FIL_SW4") (class "Default")
      (node (ref "IC18") (pin "18") (pinfunction "PA8_18") (pintype "bidirectional"))
      (node (ref "IC6") (pin "18") (pinfunction "CTL2_18") (pintype "input"))
    )
    (net (code "23") (name "GND") (class "Default")
      (node (ref "C1") (pin "2") (pinfunction "2_2") (pintype "passive"))
      (node (ref "C11") (pin "2") (pinfunction "2_2") (pintype "passive"))
      (node (ref "C12") (pin "2") (pinfunction "2_2") (pintype "passive"))
      (node (ref "C13") (pin "2") (pinfunction "2_2") (pintype "passive"))
      (node (ref "C16") (pin "2") (pinfunction "2_2") (pintype "passive"))
      (node (ref "C17") (pin "2") (pinfunction "2_2") (pintype "passive"))
      (node (ref "C19") (pin "2") (pinfunction "2_2") (pintype "passive"))
      (node (ref "C2") (pin "2") (pinfunction "2_2") (pintype "passive"))
      (node (ref "C20") (pin "2") (pinfunction "2_2") (pintype "passive"))
      (node (ref "C23") (pin "2") (pinfunction "2_2") (pintype "passive"))
      (node (ref "C24") (pin "2") (pinfunction "2_2") (pintype "passive"))
      (node (ref "C25") (pin "2") (pinfunction "2_2") (pintype "passive"))
      (node (ref "C27") (pin "2") (pinfunction "2_2") (pintype "passive"))
      (node (ref "C28") (pin "2") (pinfunction "2_2") (pintype "passive"))
      (node (ref "C4") (pin "2") (pinfunction "2_2") (pintype "passive"))
      (node (ref "C43") (pin "2") (pinfunction "2_2") (pintype "passive"))
      (node (ref "C44") (pin "2") (pinfunction "2_2") (pintype "passive"))
      (node (ref "C45") (pin "2") (pinfunction "2_2") (pintype "passive"))
      (node (ref "C46") (pin "2") (pinfunction "2_2") (pintype "passive"))
      (node (ref "C47") (pin "2") (pinfunction "2_2") (pintype "passive"))
      (node (ref "C48") (pin "2") (pinfunction "2_2") (pintype "passive"))
      (node (ref "C49") (pin "2") (pinfunction "2_2") (pintype "passive"))
      (node (ref "C50") (pin "2") (pinfunction "2_2") (pintype "passive"))
      (node (ref "C51") (pin "2") (pinfunction "2_2") (pintype "passive"))
      (node (ref "C52") (pin "2") (pinfunction "2_2") (pintype "passive"))
      (node (ref "C53") (pin "2") (pinfunction "2_2") (pintype "passive"))
      (node (ref "C54") (pin "2") (pinfunction "2_2") (pintype "passive"))
      (node (ref "C55") (pin "2") (pinfunction "2_2") (pintype "passive"))
      (node (ref "C56") (pin "2") (pinfunction "2_2") (pintype "passive"))
      (node (ref "C57") (pin "2") (pinfunction "2_2") (pintype "passive"))
      (node (ref "C58") (pin "2") (pinfunction "2_2") (pintype "passive"))
      (node (ref "C59") (pin "2") (pinfunction "2_2") (pintype "passive"))
      (node (ref "C6") (pin "2") (pinfunction "2_2") (pintype "passive"))
      (node (ref "C60") (pin "1") (pinfunction "1_1") (pintype "passive"))
      (node (ref "C61") (pin "2") (pinfunction "2_2") (pintype "passive"))
      (node (ref "C62") (pin "1") (pinfunction "1_1") (pintype "passive"))
      (node (ref "C63") (pin "2") (pinfunction "2_2") (pintype "passive"))
      (node (ref "C64") (pin "2") (pinfunction "2_2") (pintype "passive"))
      (node (ref "C65") (pin "2") (pinfunction "2_2") (pintype "passive"))
      (node (ref "C66") (pin "2") (pinfunction "2_2") (pintype "passive"))
      (node (ref "C67") (pin "2") (pinfunction "2_2") (pintype "passive"))
      (node (ref "C68") (pin "2") (pinfunction "2_2") (pintype "passive"))
      (node (ref "C69") (pin "2") (pinfunction "2_2") (pintype "passive"))
      (node (ref "C7") (pin "2") (pinfunction "2_2") (pintype "passive"))
      (node (ref "C70") (pin "2") (pinfunction "2_2") (pintype "passive"))
      (node (ref "C71") (pin "2") (pinfunction "2_2") (pintype "passive"))
      (node (ref "C72") (pin "2") (pinfunction "2_2") (pintype "passive"))
      (node (ref "C73") (pin "2") (pinfunction "2_2") (pintype "passive"))
      (node (ref "C74") (pin "2") (pinfunction "2_2") (pintype "passive"))
      (node (ref "C75") (pin "2") (pinfunction "2_2") (pintype "passive"))
      (node (ref "C76") (pin "2") (pinfunction "2_2") (pintype "passive"))
      (node (ref "C77") (pin "2") (pinfunction "2_2") (pintype "passive"))
      (node (ref "C78") (pin "2") (pinfunction "2_2") (pintype "passive"))
      (node (ref "C79") (pin "2") (pinfunction "2_2") (pintype "passive"))
      (node (ref "C8") (pin "2") (pinfunction "2_2") (pintype "passive"))
      (node (ref "C80") (pin "2") (pinfunction "2_2") (pintype "passive"))
      (node (ref "C81") (pin "2") (pinfunction "2_2") (pintype "passive"))
      (node (ref "C82") (pin "2") (pinfunction "2_2") (pintype "passive"))
      (node (ref "C83") (pin "2") (pinfunction "2_2") (pintype "passive"))
      (node (ref "C84") (pin "2") (pinfunction "2_2") (pintype "passive"))
      (node (ref "C85") (pin "2") (pinfunction "2_2") (pintype "passive"))
      (node (ref "C86") (pin "2") (pinfunction "2_2") (pintype "passive"))
      (node (ref "C87") (pin "2") (pinfunction "2_2") (pintype "passive"))
      (node (ref "C9") (pin "2") (pinfunction "2_2") (pintype "passive"))
      (node (ref "CON1") (pin "G1") (pinfunction "GND_G1") (pintype "passive"))
      (node (ref "CON1") (pin "G2") (pinfunction "GND_G2") (pintype "passive"))
      (node (ref "CON1") (pin "G3") (pinfunction "GND_G3") (pintype "passive"))
      (node (ref "CON1") (pin "G4") (pinfunction "GND_G4") (pintype "passive"))
      (node (ref "CON2") (pin "G1") (pinfunction "GND_G1") (pintype "passive"))
      (node (ref "CON2") (pin "G2") (pinfunction "GND_G2") (pintype "passive"))
      (node (ref "CON2") (pin "G3") (pinfunction "GND_G3") (pintype "passive"))
      (node (ref "CON2") (pin "G4") (pinfunction "GND_G4") (pintype "passive"))
      (node (ref "CON3") (pin "G1") (pinfunction "GND_G1") (pintype "passive"))
      (node (ref "CON3") (pin "G2") (pinfunction "GND_G2") (pintype "passive"))
      (node (ref "CON3") (pin "G3") (pinfunction "GND_G3") (pintype "passive"))
      (node (ref "CON3") (pin "G4") (pinfunction "GND_G4") (pintype "passive"))
      (node (ref "CON4") (pin "3") (pinfunction "GND_3") (pintype "power_in"))
      (node (ref "CON5") (pin "A1,B12:GND") (pinfunction "GND_A1,B12:GND") (pintype "bidirectional"))
      (node (ref "CON5") (pin "B1,A12:GND") (pinfunction "GND_B1,A12:GND") (pintype "bidirectional"))
      (node (ref "CON5") (pin "SHILED1") (pinfunction "XT_SHILED1") (pintype "bidirectional"))
      (node (ref "CON5") (pin "SHILED2") (pinfunction "XT_SHILED2") (pintype "bidirectional"))
      (node (ref "CON5") (pin "SHILED3") (pinfunction "XT_SHILED3") (pintype "bidirectional"))
      (node (ref "CON5") (pin "SHILED4") (pinfunction "XT_SHILED4") (pintype "bidirectional"))
      (node (ref "CON5") (pin "SHILED5") (pinfunction "XT_SHILED5") (pintype "bidirectional"))
      (node (ref "CON5") (pin "SHILED6") (pinfunction "XT_SHILED6") (pintype "bidirectional"))
      (node (ref "CON5") (pin "SHILED7") (pinfunction "XT_SHILED7") (pintype "bidirectional"))
      (node (ref "CON5") (pin "SHILED8") (pinfunction "XT_SHILED8") (pintype "bidirectional"))
      (node (ref "D3") (pin "K") (pinfunction "K_K") (pintype "passive"))
      (node (ref "DR1") (pin "T") (pinfunction "HT_T") (pintype "passive"))
      (node (ref "DR2") (pin "T") (pinfunction "HT_T") (pintype "passive"))
      (node (ref "DR3") (pin "T") (pinfunction "HT_T") (pintype "passive"))
      (node (ref "DR4") (pin "T") (pinfunction "HT_T") (pintype "passive"))
      (node (ref "FIL1") (pin "1") (pinfunction "GND_1") (pintype "input"))
      (node (ref "FIL1") (pin "3") (pinfunction "GND_3") (pintype "input"))
      (node (ref "FIL1") (pin "5") (pinfunction "GND_5") (pintype "input"))
      (node (ref "FIL1") (pin "7") (pinfunction "GND_7") (pintype "input"))
      (node (ref "FIL2") (pin "2") (pinfunction "GND_2") (pintype "input"))
      (node (ref "FIL2") (pin "4") (pinfunction "GND_4") (pintype "input"))
      (node (ref "FIL3") (pin "1") (pinfunction "GND_1") (pintype "input"))
      (node (ref "FIL3") (pin "3") (pinfunction "GND_3") (pintype "input"))
      (node (ref "FIL3") (pin "4") (pinfunction "GND_4") (pintype "input"))
      (node (ref "FIL3") (pin "6") (pinfunction "GND_6") (pintype "input"))
      (node (ref "FIL4") (pin "2") (pinfunction "GND_2") (pintype "input"))
      (node (ref "FIL4") (pin "4") (pinfunction "GND_4") (pintype "input"))
      (node (ref "FIL5") (pin "2") (pinfunction "GND_2") (pintype "input"))
      (node (ref "FIL5") (pin "4") (pinfunction "GND_4") (pintype "input"))
      (node (ref "FIL6") (pin "2") (pinfunction "GND_2") (pintype "input"))
      (node (ref "FIL6") (pin "4") (pinfunction "GND_4") (pintype "input"))
      (node (ref "FIL7") (pin "2") (pinfunction "GND_2") (pintype "input"))
      (node (ref "FIL7") (pin "4") (pinfunction "GND_4") (pintype "input"))
      (node (ref "FIL8") (pin "2") (pinfunction "GND_2") (pintype "input"))
      (node (ref "FIL8") (pin "4") (pinfunction "GND_4") (pintype "input"))
      (node (ref "FIL9") (pin "1") (pinfunction "GND_1") (pintype "input"))
      (node (ref "FIL9") (pin "2") (pinfunction "GND_2") (pintype "input"))
      (node (ref "FIL9") (pin "3") (pinfunction "GND_3") (pintype "input"))
      (node (ref "FIL9") (pin "5") (pinfunction "GND_5") (pintype "input"))
      (node (ref "IC1") (pin "1") (pinfunction "GND_1") (pintype "input"))
      (node (ref "IC1") (pin "10") (pinfunction "GND_10") (pintype "input"))
      (node (ref "IC1") (pin "12") (pinfunction "GND_12") (pintype "input"))
      (node (ref "IC1") (pin "13") (pinfunction "GND_13") (pintype "input"))
      (node (ref "IC1") (pin "15") (pinfunction "GND_15") (pintype "input"))
      (node (ref "IC1") (pin "19") (pinfunction "CTL3_19") (pintype "input"))
      (node (ref "IC1") (pin "2") (pinfunction "GND_2") (pintype "input"))
      (node (ref "IC1") (pin "20") (pinfunction "VSS_20") (pintype "input"))
      (node (ref "IC1") (pin "21") (pinfunction "GND_21") (pintype "input"))
      (node (ref "IC1") (pin "23") (pinfunction "GND_23") (pintype "input"))
      (node (ref "IC1") (pin "24") (pinfunction "GND_24") (pintype "input"))
      (node (ref "IC1") (pin "3") (pinfunction "GND_3") (pintype "input"))
      (node (ref "IC1") (pin "4") (pinfunction "GND_4") (pintype "input"))
      (node (ref "IC1") (pin "6") (pinfunction "GND_6") (pintype "input"))
      (node (ref "IC1") (pin "7") (pinfunction "GND_7") (pintype "input"))
      (node (ref "IC1") (pin "9") (pinfunction "GND_9") (pintype "input"))
      (node (ref "IC1") (pin "HT") (pinfunction "GND_HT") (pintype "input"))
      (node (ref "IC10") (pin "3") (pinfunction "GND_3") (pintype "input"))
      (node (ref "IC11") (pin "3") (pinfunction "GND_3") (pintype "input"))
      (node (ref "IC12") (pin "4") (pinfunction "V-_4") (pintype "input"))
      (node (ref "IC13") (pin "4") (pinfunction "V-_4") (pintype "input"))
      (node (ref "IC14") (pin "2") (pinfunction "GND_2") (pintype "input"))
      (node (ref "IC15") (pin "3") (pinfunction "GND_3") (pintype "bidirectional"))
      (node (ref "IC16") (pin "2") (pinfunction "GND_2") (pintype "input"))
      (node (ref "IC17") (pin "2") (pinfunction "GND_2") (pintype "input"))
      (node (ref "IC18") (pin "14") (pinfunction "VSSA_14") (pintype "power_in"))
      (node (ref "IC18") (pin "16") (pinfunction "VSS_2_16") (pintype "power_in"))
      (node (ref "IC18") (pin "32") (pinfunction "VSS_1_32") (pintype "power_in"))
      (node (ref "IC2") (pin "3") (pinfunction "GND_3") (pintype "power_in"))
      (node (ref "IC3") (pin "13") (pinfunction "GND_13") (pintype "input"))
      (node (ref "IC3") (pin "14") (pinfunction "GND_14") (pintype "input"))
      (node (ref "IC3") (pin "2") (pinfunction "GND_2") (pintype "input"))
      (node (ref "IC3") (pin "25") (pinfunction "GND_25") (pintype "input"))
      (node (ref "IC3") (pin "28") (pinfunction "SYSRELREQ_28") (pintype "input"))
      (node (ref "IC3") (pin "30") (pinfunction "RAMPCLK_30") (pintype "input"))
      (node (ref "IC3") (pin "31") (pinfunction "GND_31") (pintype "input"))
      (node (ref "IC3") (pin "32") (pinfunction "RAMPDIR_32") (pintype "input"))
      (node (ref "IC3") (pin "34") (pinfunction "GND_34") (pintype "input"))
      (node (ref "IC3") (pin "39") (pinfunction "GND_39") (pintype "input"))
      (node (ref "IC3") (pin "4") (pinfunction "GND_4") (pintype "input"))
      (node (ref "IC3") (pin "40") (pinfunction "GND_40") (pintype "input"))
      (node (ref "IC3") (pin "5") (pinfunction "SYNC_5") (pintype "input"))
      (node (ref "IC3") (pin "6") (pinfunction "GND_6") (pintype "input"))
      (node (ref "IC3") (pin "HT") (pinfunction "GND_HT") (pintype "input"))
      (node (ref "IC3") (pin "HT2") (pinfunction "GND_HT2") (pintype "input"))
      (node (ref "IC4") (pin "2") (pinfunction "GND_2") (pintype "power_in"))
      (node (ref "IC5") (pin "3") (pinfunction "GND_3") (pintype "power_in"))
      (node (ref "IC6") (pin "1") (pinfunction "GND_1") (pintype "input"))
      (node (ref "IC6") (pin "10") (pinfunction "GND_10") (pintype "input"))
      (node (ref "IC6") (pin "12") (pinfunction "GND_12") (pintype "input"))
      (node (ref "IC6") (pin "13") (pinfunction "GND_13") (pintype "input"))
      (node (ref "IC6") (pin "15") (pinfunction "GND_15") (pintype "input"))
      (node (ref "IC6") (pin "19") (pinfunction "CTL3_19") (pintype "input"))
      (node (ref "IC6") (pin "2") (pinfunction "GND_2") (pintype "input"))
      (node (ref "IC6") (pin "20") (pinfunction "VSS_20") (pintype "input"))
      (node (ref "IC6") (pin "21") (pinfunction "GND_21") (pintype "input"))
      (node (ref "IC6") (pin "23") (pinfunction "GND_23") (pintype "input"))
      (node (ref "IC6") (pin "24") (pinfunction "GND_24") (pintype "input"))
      (node (ref "IC6") (pin "3") (pinfunction "GND_3") (pintype "input"))
      (node (ref "IC6") (pin "4") (pinfunction "GND_4") (pintype "input"))
      (node (ref "IC6") (pin "6") (pinfunction "GND_6") (pintype "input"))
      (node (ref "IC6") (pin "7") (pinfunction "GND_7") (pintype "input"))
      (node (ref "IC6") (pin "9") (pinfunction "GND_9") (pintype "input"))
      (node (ref "IC6") (pin "HT") (pinfunction "GND_HT") (pintype "input"))
      (node (ref "IC7") (pin "1") (pinfunction "GND_1") (pintype "power_in"))
      (node (ref "IC7") (pin "11") (pinfunction "GND_11") (pintype "power_in"))
      (node (ref "IC7") (pin "14") (pinfunction "GND_14") (pintype "power_in"))
      (node (ref "IC7") (pin "17") (pinfunction "GND_17") (pintype "power_in"))
      (node (ref "IC7") (pin "18") (pinfunction "GND_18") (pintype "power_in"))
      (node (ref "IC7") (pin "2") (pinfunction "GND_2") (pintype "power_in"))
      (node (ref "IC7") (pin "20") (pinfunction "GND_20") (pintype "power_in"))
      (node (ref "IC7") (pin "23") (pinfunction "GND_23") (pintype "power_in"))
      (node (ref "IC7") (pin "5") (pinfunction "GND_5") (pintype "power_in"))
      (node (ref "IC7") (pin "7") (pinfunction "ENBL_7") (pintype "input"))
      (node (ref "IC7") (pin "8") (pinfunction "GND_8") (pintype "power_in"))
      (node (ref "IC7") (pin "HT") (pinfunction "HT_HT") (pintype "passive"))
      (node (ref "IC8") (pin "6") (pinfunction "V-_6") (pintype "input"))
      (node (ref "IC9") (pin "6") (pinfunction "V-_6") (pintype "input"))
      (node (ref "R1") (pin "1") (pinfunction "1_1") (pintype "passive"))
      (node (ref "R2") (pin "1") (pinfunction "1_1") (pintype "passive"))
      (node (ref "R22") (pin "1") (pinfunction "1_1") (pintype "passive"))
      (node (ref "R40") (pin "1") (pinfunction "1_1") (pintype "passive"))
      (node (ref "R42") (pin "1") (pinfunction "1_1") (pintype "passive"))
      (node (ref "R44") (pin "1") (pinfunction "1_1") (pintype "passive"))
      (node (ref "R45") (pin "1") (pinfunction "1_1") (pintype "passive"))
      (node (ref "R5") (pin "1") (pinfunction "1_1") (pintype "passive"))
      (node (ref "R51") (pin "1") (pinfunction "1_1") (pintype "passive"))
      (node (ref "R52") (pin "1") (pinfunction "1_1") (pintype "passive"))
      (node (ref "R6") (pin "1") (pinfunction "1_1") (pintype "passive"))
      (node (ref "T1") (pin "6") (pinfunction "GND_6") (pintype "passive"))
      (node (ref "TP2") (pin "1") (pinfunction "1_1") (pintype "passive"))
      (node (ref "TP3") (pin "1") (pinfunction "1_1") (pintype "passive"))
      (node (ref "TP5") (pin "1") (pinfunction "1_1") (pintype "passive"))
      (node (ref "TP6") (pin "1") (pinfunction "1_1") (pintype "passive"))
      (node (ref "TP7") (pin "1") (pinfunction "1_1") (pintype "passive"))
      (node (ref "TP8") (pin "1") (pinfunction "1_1") (pintype "passive"))
      (node (ref "TP9") (pin "1") (pinfunction "1_1") (pintype "passive"))
      (node (ref "X1") (pin "2") (pinfunction "GND_2") (pintype "input"))
      (node (ref "X2") (pin "2") (pinfunction "GND_2") (pintype "passive"))
      (node (ref "X2") (pin "4") (pinfunction "GND_4") (pintype "passive"))
    )
    (net (code "24") (name "MIX_IN") (class "Default")
      (node (ref "IC7") (pin "4") (pinfunction "ILO_4") (pintype "output"))
      (node (ref "R12") (pin "1") (pinfunction "1_1") (pintype "passive"))
    )
    (net (code "25") (name "MIX_IP") (class "Default")
      (node (ref "IC7") (pin "3") (pinfunction "IHI_3") (pintype "output"))
      (node (ref "R11") (pin "1") (pinfunction "1_1") (pintype "passive"))
    )
    (net (code "26") (name "MIX_QN") (class "Default")
      (node (ref "IC7") (pin "15") (pinfunction "QLO_15") (pintype "output"))
      (node (ref "R14") (pin "1") (pinfunction "1_1") (pintype "passive"))
    )
    (net (code "27") (name "MIX_QP") (class "Default")
      (node (ref "IC7") (pin "16") (pinfunction "QHI_16") (pintype "output"))
      (node (ref "R13") (pin "1") (pinfunction "1_1") (pintype "passive"))
    )
    (net (code "28") (name "Net-(C10-Pad2)") (class "Default")
      (node (ref "C10") (pin "2") (pinfunction "2_2") (pintype "passive"))
      (node (ref "R5") (pin "2") (pinfunction "2_2") (pintype "passive"))
    )
    (net (code "29") (name "Net-(C22-Pad2)") (class "Default")
      (node (ref "C22") (pin "2") (pinfunction "2_2") (pintype "passive"))
      (node (ref "R6") (pin "2") (pinfunction "2_2") (pintype "passive"))
    )
    (net (code "30") (name "Net-(C29-Pad1)") (class "Default")
      (node (ref "C29") (pin "1") (pinfunction "1_1") (pintype "passive"))
      (node (ref "R11") (pin "2") (pinfunction "2_2") (pintype "passive"))
    )
    (net (code "31") (name "Net-(C29-Pad2)") (class "Default")
      (node (ref "C29") (pin "2") (pinfunction "2_2") (pintype "passive"))
      (node (ref "C37") (pin "1") (pinfunction "1_1") (pintype "passive"))
      (node (ref "L4") (pin "1") (pinfunction "1_1") (pintype "passive"))
    )
    (net (code "32") (name "Net-(C30-Pad1)") (class "Default")
      (node (ref "C30") (pin "1") (pinfunction "1_1") (pintype "passive"))
      (node (ref "R12") (pin "2") (pinfunction "2_2") (pintype "passive"))
    )
    (net (code "33") (name "Net-(C30-Pad2)") (class "Default")
      (node (ref "C30") (pin "2") (pinfunction "2_2") (pintype "passive"))
      (node (ref "C37") (pin "2") (pinfunction "2_2") (pintype "passive"))
      (node (ref "L5") (pin "1") (pinfunction "1_1") (pintype "passive"))
    )
    (net (code "34") (name "Net-(C31-Pad1)") (class "Default")
      (node (ref "C31") (pin "1") (pinfunction "1_1") (pintype "passive"))
      (node (ref "R13") (pin "2") (pinfunction "2_2") (pintype "passive"))
    )
    (net (code "35") (name "Net-(C31-Pad2)") (class "Default")
      (node (ref "C31") (pin "2") (pinfunction "2_2") (pintype "passive"))
      (node (ref "C38") (pin "1") (pinfunction "1_1") (pintype "passive"))
      (node (ref "L6") (pin "1") (pinfunction "1_1") (pintype "passive"))
    )
    (net (code "36") (name "Net-(C32-Pad1)") (class "Default")
      (node (ref "C32") (pin "1") (pinfunction "1_1") (pintype "passive"))
      (node (ref "R14") (pin "2") (pinfunction "2_2") (pintype "passive"))
    )
    (net (code "37") (name "Net-(C32-Pad2)") (class "Default")
      (node (ref "C32") (pin "2") (pinfunction "2_2") (pintype "passive"))
      (node (ref "C38") (pin "2") (pinfunction "2_2") (pintype "passive"))
      (node (ref "L7") (pin "1") (pinfunction "1_1") (pintype "passive"))
    )
    (net (code "38") (name "Net-(C34-Pad1)") (class "Default")
      (node (ref "C34") (pin "1") (pinfunction "1_1") (pintype "passive"))
      (node (ref "R15") (pin "1") (pinfunction "1_1") (pintype "passive"))
    )
    (net (code "39") (name "Net-(C36-Pad1)") (class "Default")
      (node (ref "C36") (pin "1") (pinfunction "1_1") (pintype "passive"))
      (node (ref "R20") (pin "1") (pinfunction "1_1") (pintype "passive"))
    )
    (net (code "40") (name "Net-(C39-Pad1)") (class "Default")
      (node (ref "C39") (pin "1") (pinfunction "1_1") (pintype "passive"))
      (node (ref "L4") (pin "2") (pinfunction "2_2") (pintype "passive"))
      (node (ref "L8") (pin "1") (pinfunction "1_1") (pintype "passive"))
    )
    (net (code "41") (name "Net-(C39-Pad2)") (class "Default")
      (node (ref "C39") (pin "2") (pinfunction "2_2") (pintype "passive"))
      (node (ref "L5") (pin "2") (pinfunction "2_2") (pintype "passive"))
      (node (ref "L9") (pin "1") (pinfunction "1_1") (pintype "passive"))
    )
    (net (code "42") (name "Net-(C40-Pad1)") (class "Default")
      (node (ref "C40") (pin "1") (pinfunction "1_1") (pintype "passive"))
      (node (ref "L10") (pin "1") (pinfunction "1_1") (pintype "passive"))
      (node (ref "L6") (pin "2") (pinfunction "2_2") (pintype "passive"))
    )
    (net (code "43") (name "Net-(C40-Pad2)") (class "Default")
      (node (ref "C40") (pin "2") (pinfunction "2_2") (pintype "passive"))
      (node (ref "L11") (pin "1") (pinfunction "1_1") (pintype "passive"))
      (node (ref "L7") (pin "2") (pinfunction "2_2") (pintype "passive"))
    )
    (net (code "44") (name "Net-(CON1-PadSIG)") (class "Default")
      (node (ref "CON1") (pin "SIG") (pinfunction "SIG_SIG") (pintype "passive"))
      (node (ref "R1") (pin "2") (pinfunction "2_2") (pintype "passive"))
    )
    (net (code "45") (name "Net-(CON5-CC1)") (class "Default")
      (node (ref "CON5") (pin "A5:CC1") (pinfunction "CC1_A5:CC1") (pintype "bidirectional"))
      (node (ref "R51") (pin "2") (pinfunction "2_2") (pintype "passive"))
    )
    (net (code "46") (name "Net-(CON5-CC2)") (class "Default")
      (node (ref "CON5") (pin "B5:CC2") (pinfunction "CC2_B5:CC2") (pintype "bidirectional"))
      (node (ref "R52") (pin "2") (pinfunction "2_2") (pintype "passive"))
    )
    (net (code "47") (name "Net-(D1-PadK)") (class "Default")
      (node (ref "D1") (pin "K") (pinfunction "K_K") (pintype "passive"))
      (node (ref "R43") (pin "2") (pinfunction "2_2") (pintype "passive"))
    )
    (net (code "48") (name "Net-(D2-PadK)") (class "Default")
      (node (ref "D2") (pin "K") (pinfunction "K_K") (pintype "passive"))
      (node (ref "R44") (pin "2") (pinfunction "2_2") (pintype "passive"))
    )
    (net (code "49") (name "Net-(D3-PadA)") (class "Default")
      (node (ref "D3") (pin "A") (pinfunction "A_A") (pintype "passive"))
      (node (ref "R46") (pin "2") (pinfunction "2_2") (pintype "passive"))
    )
    (net (code "50") (name "Net-(FIL1-OUT)") (class "Default")
      (node (ref "FIL1") (pin "4") (pinfunction "OUT_4") (pintype "output"))
      (node (ref "IC1") (pin "22") (pinfunction "PC_22") (pintype "bidirectional"))
    )
    (net (code "51") (name "Net-(FIL2-IN)") (class "Default")
      (node (ref "FIL2") (pin "1") (pinfunction "IN_1") (pintype "input"))
      (node (ref "IC1") (pin "11") (pinfunction "P2_11") (pintype "bidirectional"))
    )
    (net (code "52") (name "Net-(FIL2-OUT)") (class "Default")
      (node (ref "FIL2") (pin "3") (pinfunction "OUT_3") (pintype "output"))
      (node (ref "FIL6") (pin "1") (pinfunction "IN_1") (pintype "input"))
    )
    (net (code "53") (name "Net-(FIL3-IN)") (class "Default")
      (node (ref "FIL3") (pin "5") (pinfunction "IN_5") (pintype "input"))
      (node (ref "IC1") (pin "8") (pinfunction "P3_8") (pintype "bidirectional"))
    )
    (net (code "54") (name "Net-(FIL3-OUT)") (class "Default")
      (node (ref "FIL3") (pin "2") (pinfunction "OUT_2") (pintype "output"))
      (node (ref "FIL7") (pin "1") (pinfunction "IN_1") (pintype "input"))
    )
    (net (code "55") (name "Net-(FIL4-IN)") (class "Default")
      (node (ref "FIL4") (pin "1") (pinfunction "IN_1") (pintype "input"))
      (node (ref "IC1") (pin "14") (pinfunction "P1_14") (pintype "bidirectional"))
    )
    (net (code "56") (name "Net-(FIL4-OUT)") (class "Default")
      (node (ref "FIL4") (pin "3") (pinfunction "OUT_3") (pintype "output"))
      (node (ref "FIL8") (pin "1") (pinfunction "IN_1") (pintype "input"))
    )
    (net (code "57") (name "Net-(FIL5-IN)") (class "Default")
      (node (ref "FIL5") (pin "1") (pinfunction "IN_1") (pintype "input"))
      (node (ref "IC1") (pin "5") (pinfunction "P4_5") (pintype "bidirectional"))
    )
    (net (code "58") (name "Net-(FIL5-OUT)") (class "Default")
      (node (ref "FIL5") (pin "3") (pinfunction "OUT_3") (pintype "output"))
      (node (ref "FIL9") (pin "6") (pinfunction "IN_6") (pintype "input"))
    )
    (net (code "59") (name "Net-(FIL6-OUT)") (class "Default")
      (node (ref "FIL6") (pin "3") (pinfunction "OUT_3") (pintype "output"))
      (node (ref "IC6") (pin "8") (pinfunction "P3_8") (pintype "bidirectional"))
    )
    (net (code "60") (name "Net-(FIL7-OUT)") (class "Default")
      (node (ref "FIL7") (pin "3") (pinfunction "OUT_3") (pintype "output"))
      (node (ref "IC6") (pin "11") (pinfunction "P2_11") (pintype "bidirectional"))
    )
    (net (code "61") (name "Net-(FIL8-OUT)") (class "Default")
      (node (ref "FIL8") (pin "3") (pinfunction "OUT_3") (pintype "output"))
      (node (ref "IC6") (pin "5") (pinfunction "P4_5") (pintype "bidirectional"))
    )
    (net (code "62") (name "Net-(FIL9-OUT)") (class "Default")
      (node (ref "FIL9") (pin "4") (pinfunction "OUT_4") (pintype "output"))
      (node (ref "IC6") (pin "14") (pinfunction "P1_14") (pintype "bidirectional"))
    )
    (net (code "63") (name "Net-(IC2-RF1)") (class "Default")
      (node (ref "C15") (pin "1") (pinfunction "1_1") (pintype "passive"))
      (node (ref "IC2") (pin "2") (pinfunction "RF1_2") (pintype "passive"))
    )
    (net (code "64") (name "Net-(IC2-RF2)") (class "Default")
      (node (ref "C14") (pin "1") (pinfunction "1_1") (pintype "passive"))
      (node (ref "IC2") (pin "4") (pinfunction "RF2_4") (pintype "passive"))
    )
    (net (code "65") (name "Net-(IC2-RFC)") (class "Default")
      (node (ref "C5") (pin "2") (pinfunction "2_2") (pintype "passive"))
      (node (ref "IC2") (pin "6") (pinfunction "RFC_6") (pintype "passive"))
    )
    (net (code "66") (name "Net-(IC3-CE)") (class "Default")
      (node (ref "IC3") (pin "1") (pinfunction "CE_1") (pintype "input"))
      (node (ref "R3") (pin "1") (pinfunction "1_1") (pintype "passive"))
    )
    (net (code "67") (name "Net-(IC3-OSCINM)") (class "Default")
      (node (ref "C4") (pin "1") (pinfunction "1_1") (pintype "passive"))
      (node (ref "IC3") (pin "9") (pinfunction "OSCINM_9") (pintype "input"))
    )
    (net (code "68") (name "Net-(IC3-OSCINP)") (class "Default")
      (node (ref "C3") (pin "1") (pinfunction "1_1") (pintype "passive"))
      (node (ref "IC3") (pin "8") (pinfunction "OSCINP_8") (pintype "input"))
    )
    (net (code "69") (name "Net-(IC3-VBIASVARAC)") (class "Default")
      (node (ref "C13") (pin "1") (pinfunction "1_1") (pintype "passive"))
      (node (ref "IC3") (pin "33") (pinfunction "VBIASVARAC_33") (pintype "passive"))
    )
    (net (code "70") (name "Net-(IC3-VBIASVCO)") (class "Default")
      (node (ref "C6") (pin "1") (pinfunction "1_1") (pintype "passive"))
      (node (ref "IC3") (pin "3") (pinfunction "VBIASVCO_3") (pintype "passive"))
    )
    (net (code "71") (name "Net-(IC3-VBIASVCO2)") (class "Default")
      (node (ref "C17") (pin "1") (pinfunction "1_1") (pintype "passive"))
      (node (ref "IC3") (pin "27") (pinfunction "VBIASVCO2_27") (pintype "passive"))
    )
    (net (code "72") (name "Net-(IC3-VREFVCO)") (class "Default")
      (node (ref "C12") (pin "1") (pinfunction "1_1") (pintype "passive"))
      (node (ref "IC3") (pin "36") (pinfunction "VREFVCO_36") (pintype "passive"))
    )
    (net (code "73") (name "Net-(IC3-VREFVCO2)") (class "Default")
      (node (ref "C16") (pin "1") (pinfunction "1_1") (pintype "passive"))
      (node (ref "IC3") (pin "29") (pinfunction "VREFVCO2_29") (pintype "passive"))
    )
    (net (code "74") (name "Net-(IC3-VREGIN)") (class "Default")
      (node (ref "C8") (pin "1") (pinfunction "1_1") (pintype "passive"))
      (node (ref "IC3") (pin "10") (pinfunction "VREGIN_10") (pintype "passive"))
    )
    (net (code "75") (name "Net-(IC3-VREGVCO)") (class "Default")
      (node (ref "C11") (pin "1") (pinfunction "1_1") (pintype "passive"))
      (node (ref "IC3") (pin "38") (pinfunction "VREGVCO_38") (pintype "passive"))
    )
    (net (code "76") (name "Net-(IC4-IN)") (class "Default")
      (node (ref "C14") (pin "2") (pinfunction "2_2") (pintype "passive"))
      (node (ref "IC4") (pin "1") (pinfunction "IN_1") (pintype "input"))
    )
    (net (code "77") (name "Net-(IC4-OUT)") (class "Default")
      (node (ref "C18") (pin "1") (pinfunction "1_1") (pintype "passive"))
      (node (ref "IC4") (pin "3") (pinfunction "OUT_3") (pintype "output"))
      (node (ref "L3") (pin "2") (pinfunction "2_2") (pintype "passive"))
    )
    (net (code "78") (name "Net-(IC5-RF1)") (class "Default")
      (node (ref "C18") (pin "2") (pinfunction "2_2") (pintype "passive"))
      (node (ref "IC5") (pin "2") (pinfunction "RF1_2") (pintype "passive"))
    )
    (net (code "79") (name "Net-(IC5-RF2)") (class "Default")
      (node (ref "C15") (pin "2") (pinfunction "2_2") (pintype "passive"))
      (node (ref "IC5") (pin "4") (pinfunction "RF2_4") (pintype "passive"))
    )
    (net (code "80") (name "Net-(IC5-RFC)") (class "Default")
      (node (ref "C26") (pin "1") (pinfunction "1_1") (pintype "passive"))
      (node (ref "IC5") (pin "6") (pinfunction "RFC_6") (pintype "passive"))
    )
    (net (code "81") (name "Net-(IC7-LOIN)") (class "Default")
      (node (ref "IC7") (pin "10") (pinfunction "LOIN_10") (pintype "input"))
      (node (ref "R20") (pin "2") (pinfunction "2_2") (pintype "passive"))
    )
    (net (code "82") (name "Net-(IC7-LOIP)") (class "Default")
      (node (ref "IC7") (pin "9") (pinfunction "LOIP_9") (pintype "input"))
      (node (ref "R15") (pin "2") (pinfunction "2_2") (pintype "passive"))
    )
    (net (code "83") (name "Net-(IC7-RFIN)") (class "Default")
      (node (ref "C35") (pin "1") (pinfunction "1_1") (pintype "passive"))
      (node (ref "IC7") (pin "21") (pinfunction "RFIN_21") (pintype "input"))
    )
    (net (code "84") (name "Net-(IC7-RFIP)") (class "Default")
      (node (ref "C33") (pin "1") (pinfunction "1_1") (pintype "passive"))
      (node (ref "IC7") (pin "22") (pinfunction "RFIP_22") (pintype "input"))
    )
    (net (code "85") (name "Net-(IC8A-+IN)") (class "Default")
      (node (ref "IC8") (pin "8") (pinfunction "+IN_8") (pintype "input"))
      (node (ref "R16") (pin "1") (pinfunction "1_1") (pintype "passive"))
      (node (ref "R7") (pin "2") (pinfunction "2_2") (pintype "passive"))
    )
    (net (code "86") (name "Net-(IC8A--IN)") (class "Default")
      (node (ref "IC8") (pin "1") (pinfunction "-IN_1") (pintype "input"))
      (node (ref "R17") (pin "1") (pinfunction "1_1") (pintype "passive"))
      (node (ref "R8") (pin "2") (pinfunction "2_2") (pintype "passive"))
    )
    (net (code "87") (name "Net-(IC9A-+IN)") (class "Default")
      (node (ref "IC9") (pin "8") (pinfunction "+IN_8") (pintype "input"))
      (node (ref "R18") (pin "1") (pinfunction "1_1") (pintype "passive"))
      (node (ref "R9") (pin "2") (pinfunction "2_2") (pintype "passive"))
    )
    (net (code "88") (name "Net-(IC9A--IN)") (class "Default")
      (node (ref "IC9") (pin "1") (pinfunction "-IN_1") (pintype "input"))
      (node (ref "R10") (pin "2") (pinfunction "2_2") (pintype "passive"))
      (node (ref "R19") (pin "1") (pinfunction "1_1") (pintype "passive"))
    )
    (net (code "89") (name "Net-(IC10-A)") (class "Default")
      (node (ref "IC10") (pin "1") (pinfunction "A_1") (pintype "bidirectional"))
      (node (ref "R25") (pin "2") (pinfunction "2_2") (pintype "passive"))
      (node (ref "R27") (pin "1") (pinfunction "1_1") (pintype "passive"))
    )
    (net (code "90") (name "Net-(IC10-B)") (class "Default")
      (node (ref "IC10") (pin "2") (pinfunction "B_2") (pintype "bidirectional"))
      (node (ref "R25") (pin "1") (pinfunction "1_1") (pintype "passive"))
      (node (ref "R28") (pin "1") (pinfunction "1_1") (pintype "passive"))
    )
    (net (code "91") (name "Net-(IC11-A)") (class "Default")
      (node (ref "IC11") (pin "1") (pinfunction "A_1") (pintype "bidirectional"))
      (node (ref "R26") (pin "2") (pinfunction "2_2") (pintype "passive"))
      (node (ref "R29") (pin "1") (pinfunction "1_1") (pintype "passive"))
    )
    (net (code "92") (name "Net-(IC11-B)") (class "Default")
      (node (ref "IC11") (pin "2") (pinfunction "B_2") (pintype "bidirectional"))
      (node (ref "R26") (pin "1") (pinfunction "1_1") (pintype "passive"))
      (node (ref "R30") (pin "1") (pinfunction "1_1") (pintype "passive"))
    )
    (net (code "93") (name "Net-(IC12A-+IN)") (class "Default")
      (node (ref "IC12") (pin "3") (pinfunction "+IN_3") (pintype "input"))
      (node (ref "IC8") (pin "5") (pinfunction "-OUT_5") (pintype "output"))
      (node (ref "R16") (pin "2") (pinfunction "2_2") (pintype "passive"))
    )
    (net (code "94") (name "Net-(IC12A--IN)") (class "Default")
      (node (ref "IC12") (pin "2") (pinfunction "-IN_2") (pintype "input"))
      (node (ref "R27") (pin "2") (pinfunction "2_2") (pintype "passive"))
      (node (ref "R31") (pin "2") (pinfunction "2_2") (pintype "passive"))
    )
    (net (code "95") (name "Net-(IC12A-OUT)") (class "Default")
      (node (ref "IC12") (pin "1") (pinfunction "OUT_1") (pintype "output"))
      (node (ref "R31") (pin "1") (pinfunction "1_1") (pintype "passive"))
      (node (ref "R35") (pin "1") (pinfunction "1_1") (pintype "passive"))
    )
    (net (code "96") (name "Net-(IC12B-+IN)") (class "Default")
      (node (ref "IC12") (pin "5") (pinfunction "+IN_5") (pintype "input"))
      (node (ref "IC8") (pin "4") (pinfunction "+OUT_4") (pintype "output"))
      (node (ref "R17") (pin "2") (pinfunction "2_2") (pintype "passive"))
    )
    (net (code "97") (name "Net-(IC12B--IN)") (class "Default")
      (node (ref "IC12") (pin "6") (pinfunction "-IN_6") (pintype "input"))
      (node (ref "R28") (pin "2") (pinfunction "2_2") (pintype "passive"))
      (node (ref "R32") (pin "2") (pinfunction "2_2") (pintype "passive"))
    )
    (net (code "98") (name "Net-(IC12B-OUT)") (class "Default")
      (node (ref "IC12") (pin "7") (pinfunction "OUT_7") (pintype "output"))
      (node (ref "R32") (pin "1") (pinfunction "1_1") (pintype "passive"))
      (node (ref "R36") (pin "1") (pinfunction "1_1") (pintype "passive"))
    )
    (net (code "99") (name "Net-(IC13A-+IN)") (class "Default")
      (node (ref "IC13") (pin "3") (pinfunction "+IN_3") (pintype "input"))
      (node (ref "IC9") (pin "5") (pinfunction "-OUT_5") (pintype "output"))
      (node (ref "R18") (pin "2") (pinfunction "2_2") (pintype "passive"))
    )
    (net (code "100") (name "Net-(IC13A--IN)") (class "Default")
      (node (ref "IC13") (pin "2") (pinfunction "-IN_2") (pintype "input"))
      (node (ref "R29") (pin "2") (pinfunction "2_2") (pintype "passive"))
      (node (ref "R33") (pin "2") (pinfunction "2_2") (pintype "passive"))
    )
    (net (code "101") (name "Net-(IC13A-OUT)") (class "Default")
      (node (ref "IC13") (pin "1") (pinfunction "OUT_1") (pintype "output"))
      (node (ref "R33") (pin "1") (pinfunction "1_1") (pintype "passive"))
      (node (ref "R37") (pin "1") (pinfunction "1_1") (pintype "passive"))
    )
    (net (code "102") (name "Net-(IC13B-+IN)") (class "Default")
      (node (ref "IC13") (pin "5") (pinfunction "+IN_5") (pintype "input"))
      (node (ref "IC9") (pin "4") (pinfunction "+OUT_4") (pintype "output"))
      (node (ref "R19") (pin "2") (pinfunction "2_2") (pintype "passive"))
    )
    (net (code "103") (name "Net-(IC13B--IN)") (class "Default")
      (node (ref "IC13") (pin "6") (pinfunction "-IN_6") (pintype "input"))
      (node (ref "R30") (pin "2") (pinfunction "2_2") (pintype "passive"))
      (node (ref "R34") (pin "2") (pinfunction "2_2") (pintype "passive"))
    )
    (net (code "104") (name "Net-(IC13B-OUT)") (class "Default")
      (node (ref "IC13") (pin "7") (pinfunction "OUT_7") (pintype "output"))
      (node (ref "R34") (pin "1") (pinfunction "1_1") (pintype "passive"))
      (node (ref "R38") (pin "1") (pinfunction "1_1") (pintype "passive"))
    )
    (net (code "105") (name "Net-(IC14-BYPASS)") (class "Default")
      (node (ref "C76") (pin "1") (pinfunction "1_1") (pintype "passive"))
      (node (ref "IC14") (pin "4") (pinfunction "BYPASS_4") (pintype "passive"))
    )
    (net (code "106") (name "Net-(IC15-OUT)") (class "Default")
      (node (ref "IC15") (pin "2") (pinfunction "OUT_2") (pintype "bidirectional"))
      (node (ref "R43") (pin "1") (pinfunction "1_1") (pintype "passive"))
    )
    (net (code "107") (name "Net-(IC15-REF)") (class "Default")
      (node (ref "IC15") (pin "1") (pinfunction "REF_1") (pintype "input"))
      (node (ref "R41") (pin "1") (pinfunction "1_1") (pintype "passive"))
      (node (ref "R42") (pin "2") (pinfunction "2_2") (pintype "passive"))
    )
    (net (code "108") (name "Net-(IC16-BYPASS)") (class "Default")
      (node (ref "C81") (pin "1") (pinfunction "1_1") (pintype "passive"))
      (node (ref "IC16") (pin "4") (pinfunction "BYPASS_4") (pintype "passive"))
    )
    (net (code "109") (name "Net-(IC17-BYPASS)") (class "Default")
      (node (ref "C82") (pin "1") (pinfunction "1_1") (pintype "passive"))
      (node (ref "IC17") (pin "4") (pinfunction "BYPASS_4") (pintype "passive"))
    )
    (net (code "110") (name "Net-(IC18-BOOT0)") (class "Default")
      (node (ref "IC18") (pin "31") (pinfunction "BOOT0_31") (pintype "input"))
      (node (ref "R45") (pin "2") (pinfunction "2_2") (pintype "passive"))
      (node (ref "SW1") (pin "3") (pinfunction "2_3") (pintype "passive"))
      (node (ref "SW1") (pin "4") (pinfunction "2_4") (pintype "passive"))
    )
    (net (code "111") (name "Net-(IC18-NRST)") (class "Default")
      (node (ref "C79") (pin "1") (pinfunction "1_1") (pintype "passive"))
      (node (ref "IC18") (pin "4") (pinfunction "NRST_4") (pintype "bidirectional"))
    )
    (net (code "112") (name "Net-(IC18-PA5)") (class "Default")
      (node (ref "IC18") (pin "10") (pinfunction "PA5_10") (pintype "bidirectional"))
      (node (ref "R47") (pin "1") (pinfunction "1_1") (pintype "passive"))
    )
    (net (code "113") (name "Net-(IC18-PA6)") (class "Default")
      (node (ref "IC18") (pin "11") (pinfunction "PA6_11") (pintype "bidirectional"))
      (node (ref "R48") (pin "1") (pinfunction "1_1") (pintype "passive"))
    )
    (net (code "114") (name "Net-(IC18-PA7)") (class "Default")
      (node (ref "IC18") (pin "12") (pinfunction "PA7_12") (pintype "bidirectional"))
      (node (ref "R49") (pin "1") (pinfunction "1_1") (pintype "passive"))
    )
    (net (code "115") (name "Net-(IC18-PB0)") (class "Default")
      (node (ref "IC18") (pin "13") (pinfunction "PB0_13") (pintype "bidirectional"))
      (node (ref "R50") (pin "1") (pinfunction "1_1") (pintype "passive"))
    )
    (net (code "116") (name "Net-(IC18-PF0{slash}OSC_IN)") (class "Default")
      (node (ref "C75") (pin "1") (pinfunction "1_1") (pintype "passive"))
      (node (ref "IC18") (pin "2") (pinfunction "PF0/OSC_IN_2") (pintype "bidirectional"))
      (node (ref "X2") (pin "3") (pinfunction "2_3") (pintype "passive"))
    )
    (net (code "117") (name "Net-(IC18-PF1_OSC_OUT)") (class "Default")
      (node (ref "C78") (pin "1") (pinfunction "1_1") (pintype "passive"))
      (node (ref "IC18") (pin "3") (pinfunction "PF1_OSC_OUT_3") (pintype "bidirectional"))
      (node (ref "X2") (pin "1") (pinfunction "1_1") (pintype "passive"))
    )
    (net (code "118") (name "Net-(L1-Pad2)") (class "Default")
      (node (ref "L1") (pin "2") (pinfunction "2_2") (pintype "passive"))
      (node (ref "R2") (pin "2") (pinfunction "2_2") (pintype "passive"))
    )
    (net (code "119") (name "Net-(L2-Pad2)") (class "Default")
      (node (ref "L2") (pin "2") (pinfunction "2_2") (pintype "passive"))
      (node (ref "L3") (pin "1") (pinfunction "1_1") (pintype "passive"))
    )
    (net (code "120") (name "Net-(T1-OUTN)") (class "Default")
      (node (ref "C35") (pin "2") (pinfunction "2_2") (pintype "passive"))
      (node (ref "T1") (pin "4") (pinfunction "OUTN_4") (pintype "passive"))
    )
    (net (code "121") (name "Net-(T1-OUTP)") (class "Default")
      (node (ref "C33") (pin "2") (pinfunction "2_2") (pintype "passive"))
      (node (ref "T1") (pin "3") (pinfunction "OUTP_3") (pintype "passive"))
    )
    (net (code "122") (name "Net-(X1-OUT)") (class "Default")
      (node (ref "C3") (pin "2") (pinfunction "2_2") (pintype "passive"))
      (node (ref "X1") (pin "3") (pinfunction "OUT_3") (pintype "output"))
    )
    (net (code "123") (name "PGA_SW") (class "Default")
      (node (ref "IC10") (pin "4") (pinfunction "S_4") (pintype "input"))
      (node (ref "IC11") (pin "4") (pinfunction "S_4") (pintype "input"))
      (node (ref "IC18") (pin "9") (pinfunction "PA4_9") (pintype "bidirectional"))
      (node (ref "R46") (pin "1") (pinfunction "1_1") (pintype "passive"))
    )
    (net (code "124") (name "PLL_OUT1N") (class "Default")
      (node (ref "C22") (pin "1") (pinfunction "1_1") (pintype "passive"))
      (node (ref "IC3") (pin "22") (pinfunction "RFOUTAM_22") (pintype "output"))
    )
    (net (code "125") (name "PLL_OUT1P") (class "Default")
      (node (ref "C21") (pin "1") (pinfunction "1_1") (pintype "passive"))
      (node (ref "IC3") (pin "23") (pinfunction "RFOUTAP_23") (pintype "output"))
    )
    (net (code "126") (name "PLL_OUT2N") (class "Default")
      (node (ref "C36") (pin "2") (pinfunction "2_2") (pintype "passive"))
      (node (ref "IC3") (pin "18") (pinfunction "RFOUTBM_18") (pintype "output"))
    )
    (net (code "127") (name "PLL_OUT2P") (class "Default")
      (node (ref "C34") (pin "2") (pinfunction "2_2") (pintype "passive"))
      (node (ref "IC3") (pin "19") (pinfunction "RFOUTBP_19") (pintype "output"))
    )
    (net (code "128") (name "PLL_SPI_CS") (class "Default")
      (node (ref "IC3") (pin "24") (pinfunction "CSB_24") (pintype "input"))
      (node (ref "R50") (pin "2") (pinfunction "2_2") (pintype "passive"))
    )
    (net (code "129") (name "PLL_SPI_MISO") (class "Default")
      (node (ref "D2") (pin "A") (pinfunction "A_A") (pintype "passive"))
      (node (ref "IC3") (pin "20") (pinfunction "MUXOUT_20") (pintype "output"))
      (node (ref "R48") (pin "2") (pinfunction "2_2") (pintype "passive"))
    )
    (net (code "130") (name "PLL_SPI_MOSI") (class "Default")
      (node (ref "IC3") (pin "17") (pinfunction "SDI_17") (pintype "input"))
      (node (ref "R49") (pin "2") (pinfunction "2_2") (pintype "passive"))
    )
    (net (code "131") (name "PLL_SPI_SCK") (class "Default")
      (node (ref "IC3") (pin "16") (pinfunction "SCK_16") (pintype "input"))
      (node (ref "R47") (pin "2") (pinfunction "2_2") (pintype "passive"))
    )
    (net (code "132") (name "PLL_VCTRL") (class "Default")
      (node (ref "C7") (pin "1") (pinfunction "1_1") (pintype "passive"))
      (node (ref "IC3") (pin "35") (pinfunction "VTUNE_35") (pintype "input"))
      (node (ref "R4") (pin "1") (pinfunction "1_1") (pintype "passive"))
    )
    (net (code "133") (name "RFIN_SW1") (class "Default")
      (node (ref "IC18") (pin "29") (pinfunction "PB6_29") (pintype "bidirectional"))
      (node (ref "IC2") (pin "5") (pinfunction "VCTL_5") (pintype "input"))
    )
    (net (code "134") (name "RFIN_SW2") (class "Default")
      (node (ref "IC18") (pin "30") (pinfunction "PB7_30") (pintype "bidirectional"))
      (node (ref "IC5") (pin "5") (pinfunction "VCTL_5") (pintype "input"))
    )
    (net (code "135") (name "SWCLK") (class "Default")
      (node (ref "CON4") (pin "1") (pinfunction "SWCLK_1") (pintype "bidirectional"))
      (node (ref "IC18") (pin "24") (pinfunction "PA14/SWCLK_24") (pintype "bidirectional"))
    )
    (net (code "136") (name "SWDIO") (class "Default")
      (node (ref "CON4") (pin "4") (pinfunction "SWDIO_4") (pintype "bidirectional"))
      (node (ref "IC18") (pin "23") (pinfunction "PA13/SWDIO_23") (pintype "bidirectional"))
    )
    (net (code "137") (name "UART_RX") (class "Default")
      (node (ref "CON4") (pin "2") (pinfunction "~{RST}_2") (pintype "bidirectional"))
      (node (ref "IC18") (pin "25") (pinfunction "PA15_25") (pintype "bidirectional"))
    )
    (net (code "138") (name "UART_TX") (class "Default")
      (node (ref "CON4") (pin "5") (pinfunction "TX_5") (pintype "bidirectional"))
      (node (ref "IC18") (pin "26") (pinfunction "PB3_26") (pintype "bidirectional"))
    )
    (net (code "139") (name "USB_DM") (class "Default")
      (node (ref "CON5") (pin "A7:DN1") (pinfunction "D-_A7:DN1") (pintype "bidirectional"))
      (node (ref "CON5") (pin "B7:DN2") (pinfunction "D-_B7:DN2") (pintype "bidirectional"))
      (node (ref "IC18") (pin "21") (pinfunction "PA11_21") (pintype "bidirectional"))
    )
    (net (code "140") (name "USB_DP") (class "Default")
      (node (ref "CON5") (pin "A6:DP1") (pinfunction "D+_A6:DP1") (pintype "bidirectional"))
      (node (ref "CON5") (pin "B6:DP2") (pinfunction "D+_B6:DP2") (pintype "bidirectional"))
      (node (ref "IC18") (pin "22") (pinfunction "PA12_22") (pintype "bidirectional"))
    )
    (net (code "141") (name "USB_VBUS") (class "Default")
      (node (ref "CON5") (pin "A4,B9:VBUS") (pinfunction "VBUS_A4,B9:VBUS") (pintype "output"))
      (node (ref "CON5") (pin "B4,A9:VBUS") (pinfunction "VBUS_B4,A9:VBUS") (pintype "output"))
      (node (ref "FB6") (pin "1") (pinfunction "1_1") (pintype "passive"))
    )
    (net (code "142") (name "VCC_HFAMP") (class "Default")
      (node (ref "C44") (pin "1") (pinfunction "1_1") (pintype "passive"))
      (node (ref "C49") (pin "1") (pinfunction "1_1") (pintype "passive"))
      (node (ref "C54") (pin "1") (pinfunction "1_1") (pintype "passive"))
      (node (ref "FB3") (pin "2") (pinfunction "2_2") (pintype "passive"))
      (node (ref "L2") (pin "1") (pinfunction "1_1") (pintype "passive"))
    )
    (net (code "143") (name "VCC_MIX") (class "Default")
      (node (ref "C43") (pin "1") (pinfunction "1_1") (pintype "passive"))
      (node (ref "C48") (pin "1") (pinfunction "1_1") (pintype "passive"))
      (node (ref "C53") (pin "1") (pinfunction "1_1") (pintype "passive"))
      (node (ref "C57") (pin "1") (pinfunction "1_1") (pintype "passive"))
      (node (ref "C59") (pin "1") (pinfunction "1_1") (pintype "passive"))
      (node (ref "C64") (pin "1") (pinfunction "1_1") (pintype "passive"))
      (node (ref "C66") (pin "1") (pinfunction "1_1") (pintype "passive"))
      (node (ref "FB2") (pin "2") (pinfunction "2_2") (pintype "passive"))
      (node (ref "IC7") (pin "13") (pinfunction "VCC_13") (pintype "power_in"))
      (node (ref "IC7") (pin "24") (pinfunction "VCC_24") (pintype "power_in"))
      (node (ref "IC7") (pin "6") (pinfunction "VCC_6") (pintype "power_in"))
      (node (ref "R21") (pin "2") (pinfunction "2_2") (pintype "passive"))
    )
    (net (code "144") (name "VCC_PLL") (class "Default")
      (node (ref "C19") (pin "1") (pinfunction "1_1") (pintype "passive"))
      (node (ref "C20") (pin "1") (pinfunction "1_1") (pintype "passive"))
      (node (ref "C23") (pin "1") (pinfunction "1_1") (pintype "passive"))
      (node (ref "C24") (pin "1") (pinfunction "1_1") (pintype "passive"))
      (node (ref "C25") (pin "1") (pinfunction "1_1") (pintype "passive"))
      (node (ref "C27") (pin "1") (pinfunction "1_1") (pintype "passive"))
      (node (ref "C28") (pin "1") (pinfunction "1_1") (pintype "passive"))
      (node (ref "C85") (pin "1") (pinfunction "1_1") (pintype "passive"))
      (node (ref "C87") (pin "1") (pinfunction "1_1") (pintype "passive"))
      (node (ref "FB1") (pin "1") (pinfunction "1_1") (pintype "passive"))
      (node (ref "IC17") (pin "5") (pinfunction "VOUT_5") (pintype "output"))
      (node (ref "IC3") (pin "11") (pinfunction "VCCCP_11") (pintype "input"))
      (node (ref "IC3") (pin "15") (pinfunction "VCCMASH_15") (pintype "input"))
      (node (ref "IC3") (pin "21") (pinfunction "VCCBUF_21") (pintype "input"))
      (node (ref "IC3") (pin "26") (pinfunction "VCCVCO2_26") (pintype "passive"))
      (node (ref "IC3") (pin "37") (pinfunction "VCCVCO_37") (pintype "input"))
      (node (ref "IC3") (pin "7") (pinfunction "VCCDIG_7") (pintype "input"))
      (node (ref "R3") (pin "2") (pinfunction "2_2") (pintype "passive"))
    )
    (net (code "145") (name "VCC_RFSW1") (class "Default")
      (node (ref "C45") (pin "1") (pinfunction "1_1") (pintype "passive"))
      (node (ref "C50") (pin "1") (pinfunction "1_1") (pintype "passive"))
      (node (ref "C55") (pin "1") (pinfunction "1_1") (pintype "passive"))
      (node (ref "FB4") (pin "2") (pinfunction "2_2") (pintype "passive"))
      (node (ref "IC2") (pin "1") (pinfunction "VDD_1") (pintype "power_in"))
      (node (ref "IC5") (pin "1") (pinfunction "VDD_1") (pintype "power_in"))
    )
    (net (code "146") (name "VCC_RFSW2") (class "Default")
      (node (ref "C46") (pin "1") (pinfunction "1_1") (pintype "passive"))
      (node (ref "C51") (pin "1") (pinfunction "1_1") (pintype "passive"))
      (node (ref "C56") (pin "1") (pinfunction "1_1") (pintype "passive"))
      (node (ref "C58") (pin "1") (pinfunction "1_1") (pintype "passive"))
      (node (ref "FB5") (pin "2") (pinfunction "2_2") (pintype "passive"))
      (node (ref "IC1") (pin "16") (pinfunction "VDD_16") (pintype "input"))
      (node (ref "IC6") (pin "16") (pinfunction "VDD_16") (pintype "input"))
    )
    (net (code "147") (name "VCOM") (class "Default")
      (node (ref "C65") (pin "1") (pinfunction "1_1") (pintype "passive"))
      (node (ref "C69") (pin "1") (pinfunction "1_1") (pintype "passive"))
      (node (ref "IC8") (pin "2") (pinfunction "CM_2") (pintype "input"))
      (node (ref "IC9") (pin "2") (pinfunction "CM_2") (pintype "input"))
      (node (ref "R39") (pin "1") (pinfunction "1_1") (pintype "passive"))
      (node (ref "R40") (pin "2") (pinfunction "2_2") (pintype "passive"))
    )
    (net (code "148") (name "unconnected-(IC7-NC-Pad12)") (class "Default")
      (node (ref "IC7") (pin "12") (pinfunction "NC_12") (pintype "passive"))
    )
    (net (code "149") (name "unconnected-(IC18-PA10-Pad20)") (class "Default")
      (node (ref "IC18") (pin "20") (pinfunction "PA10_20") (pintype "bidirectional"))
    )
  )
)
